# PCB-Relay-Board-V1.net
KiCad netlist of a schematic drawn in Altium Designer
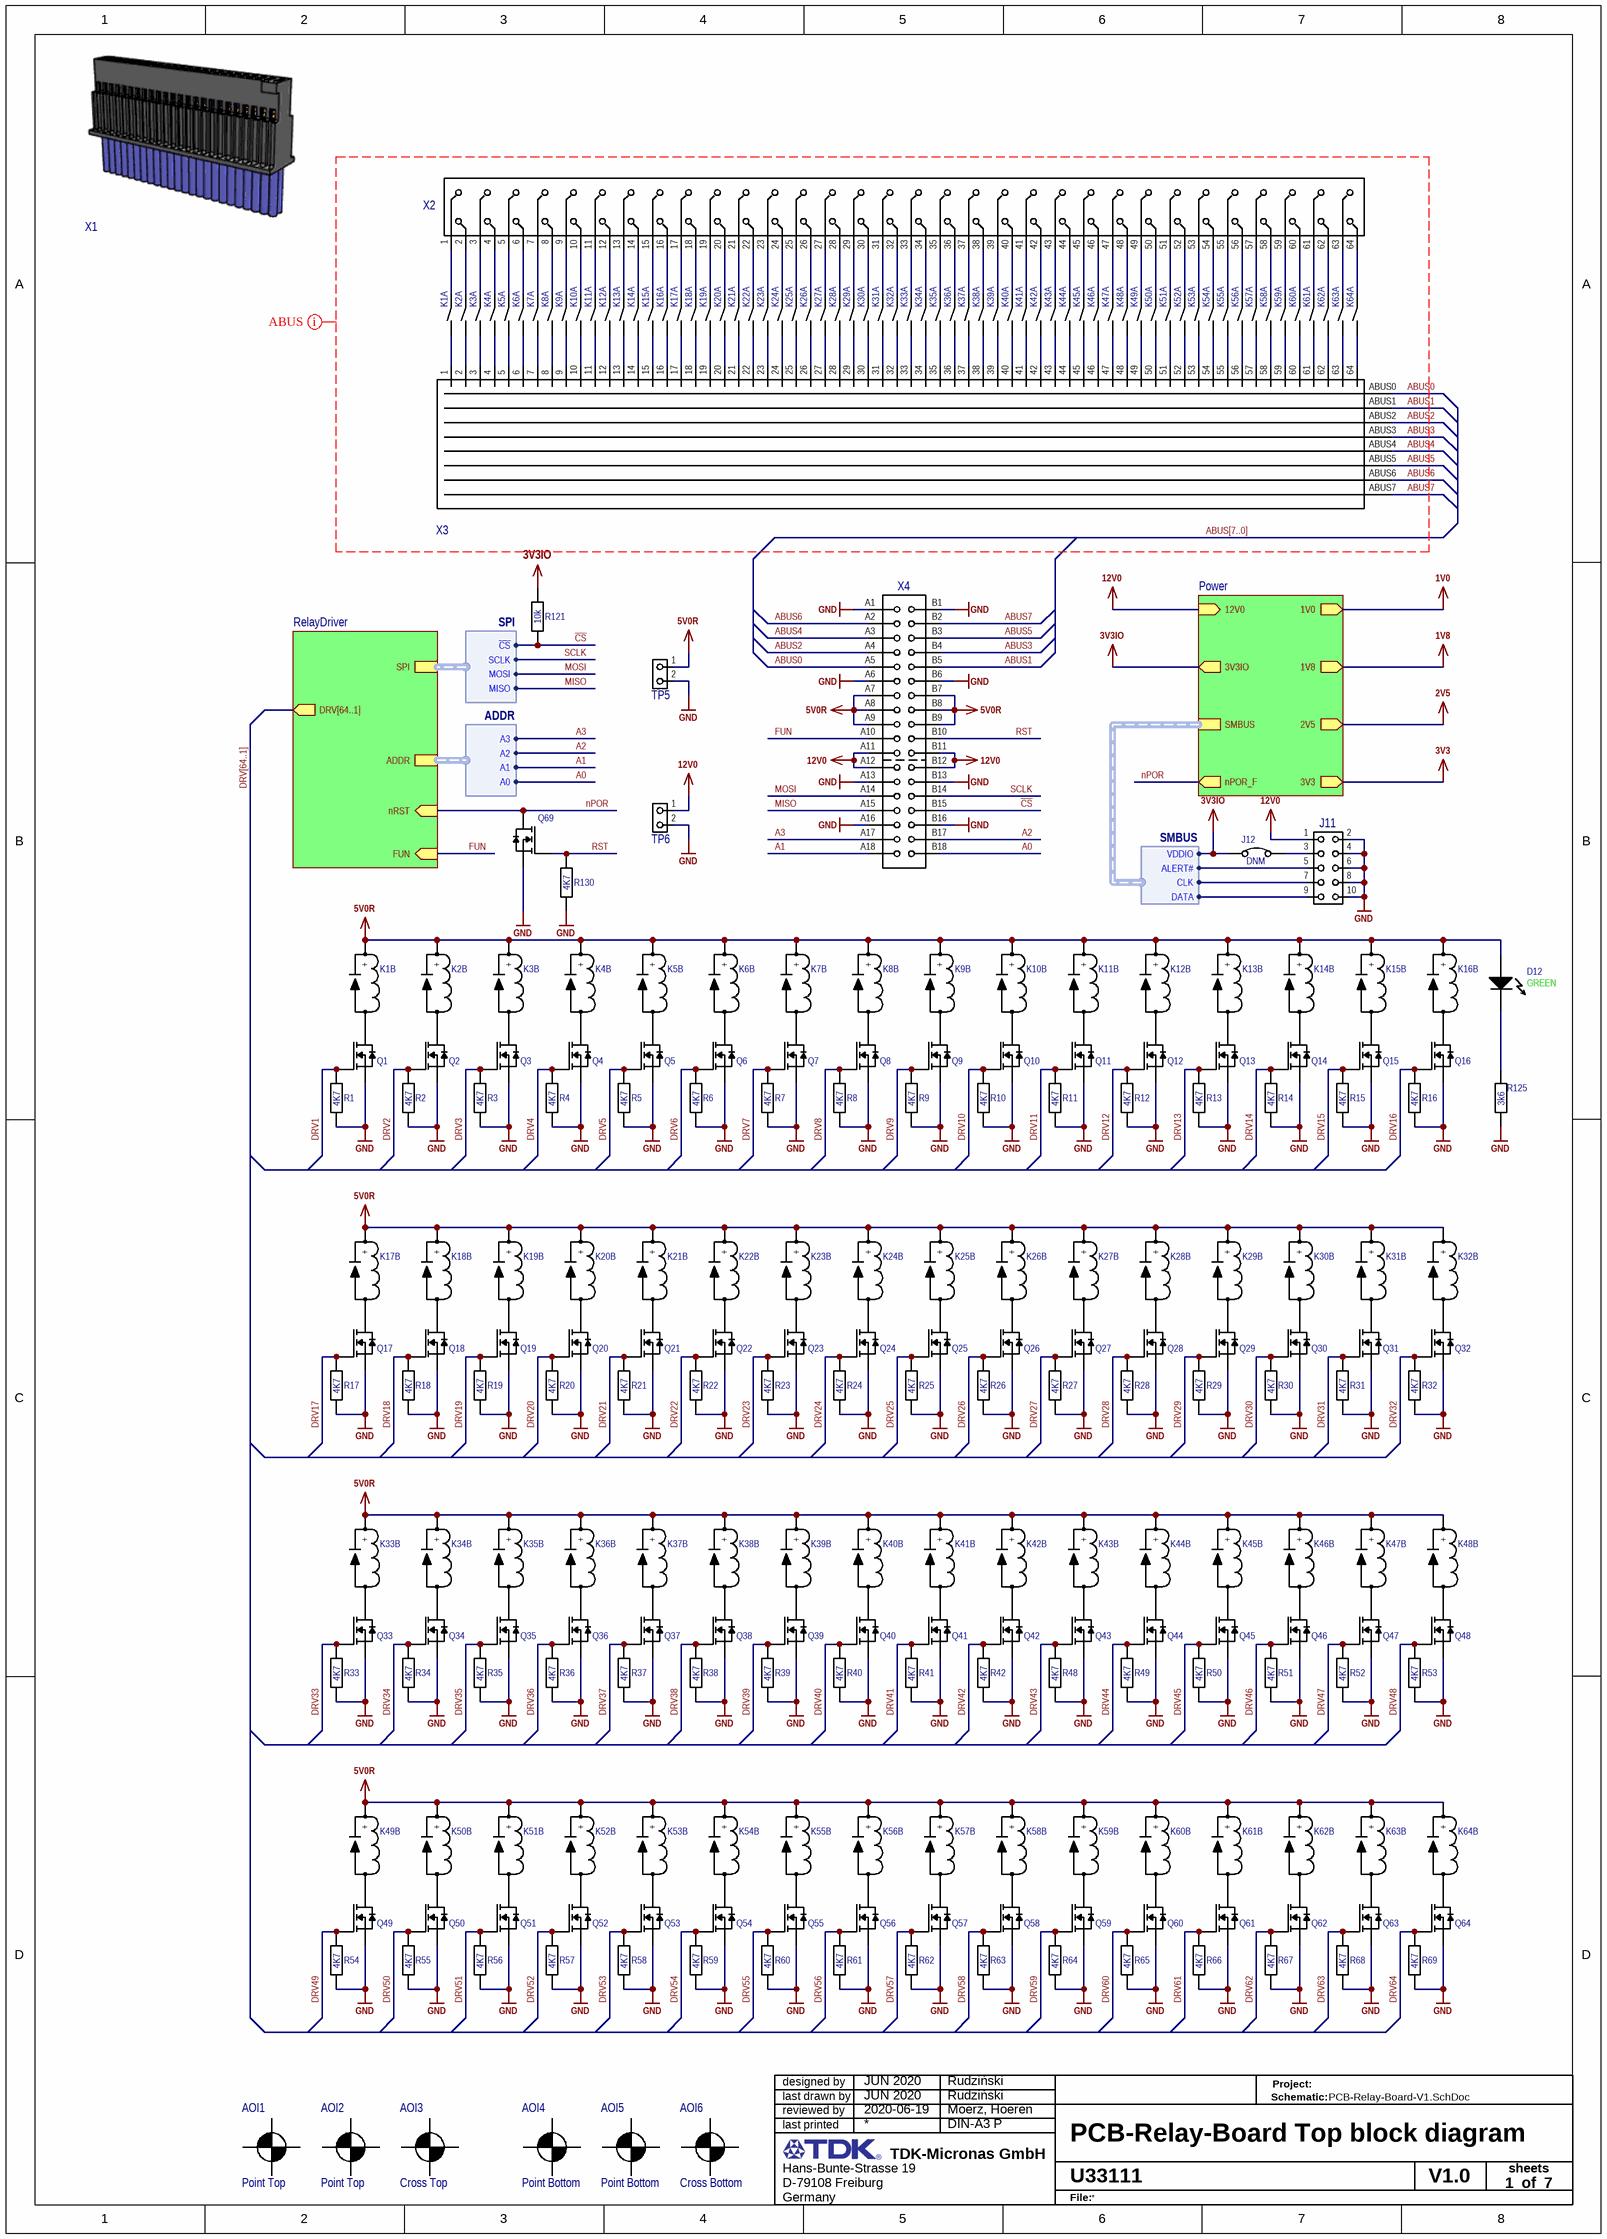
[diagram p0: PCB-Relay-Board-V1.SchDoc]

(export (version "E")
  (design (tool "Eeschema 10.0.6"))
  (components
    (comp (ref "AOI1")
      (value "AOI")
      (footprint "Fiducial Point")
      (description "Assembly AOI")
      (fields (field (name "SHAPE") "Point Top") (field (name "13. CREATED DATE/NAME") "AUG2018/Hören"))
      (libsource (lib "chickenfood") (part "Fiducial"))
    )
    (comp (ref "AOI2")
      (value "AOI")
      (footprint "Fiducial Point")
      (description "Assembly AOI")
      (fields (field (name "SHAPE") "Point Top") (field (name "13. CREATED DATE/NAME") "AUG2018/Hören"))
      (libsource (lib "chickenfood") (part "Fiducial"))
    )
    (comp (ref "AOI3")
      (value "AOI")
      (footprint "Fiducial Cross")
      (description "Assembly AOI")
      (fields (field (name "SHAPE") "Cross Top") (field (name "13. CREATED DATE/NAME") "AUG2018/Hören"))
      (libsource (lib "chickenfood") (part "Fiducial"))
    )
    (comp (ref "AOI4")
      (value "AOI")
      (footprint "Fiducial Point")
      (description "Assembly AOI")
      (fields (field (name "SHAPE") "Point Bottom") (field (name "13. CREATED DATE/NAME") "AUG2018/Hören"))
      (libsource (lib "chickenfood") (part "Fiducial"))
    )
    (comp (ref "AOI5")
      (value "AOI")
      (footprint "Fiducial Point")
      (description "Assembly AOI")
      (fields (field (name "SHAPE") "Point Bottom") (field (name "13. CREATED DATE/NAME") "AUG2018/Hören"))
      (libsource (lib "chickenfood") (part "Fiducial"))
    )
    (comp (ref "AOI6")
      (value "AOI")
      (footprint "Fiducial Cross")
      (description "Assembly AOI")
      (fields (field (name "SHAPE") "Cross Bottom") (field (name "13. CREATED DATE/NAME") "AUG2018/Hören"))
      (libsource (lib "chickenfood") (part "Fiducial"))
    )
    (comp (ref "D12")
      (value "D")
      (footprint "L0603G")
      (description "LED GREEN DIFFUSED 0603 SMD")
      (fields
        (field (name "02. DISTRIBUTOR PART NUMBER") "475-2709-6-ND")
        (field (name "07. MANUFACTURER  PART NUMBER") "LG L29K-G2J1-24-Z")
        (field (name "COLOR") "GREEN")
        (field (name "13. CREATED DATE/NAME") "AUG2018/Hören")
      )
      (libsource (lib "chickenfood") (part "LED"))
    )
    (comp (ref "J11")
      (value "J")
      (footprint "Header 100mil 5x2")
      (description ".100\" High-Temp Variable Post Height Terminal Strip")
      (fields
        (field (name "02. DISTRIBUTOR PART NUMBER") "HMTSW-105-07-G-D-240")
        (field (name "13. CREATED DATE/NAME") "AUG2018/Hören")
      )
      (libsource (lib "PCB-Tester-Board-V1") (part "Header 5x2Pins 100mil"))
    )
    (comp (ref "J12")
      (value "DNM")
      (footprint "JumperSMD")
      (description "RES SMD 0 OHM JUMPER 1/10W 0603")
      (fields
        (field (name "02. DISTRIBUTOR PART NUMBER") "311-0.0GRDKR-ND")
        (field (name "07. MANUFACTURER  PART NUMBER") "RC0603JR-070RL")
      )
      (libsource (lib "chickenfood") (part "Jumper SMD"))
    )
    (comp (ref "K1")
      (value "K")
      (footprint "118-1A")
      (description "5V Signal Relais, Normal Open")
      (fields
        (field (name "02. DISTRIBUTOR PART NUMBER") "118-1-A-5/2D")
        (field (name "13. CREATED DATE/NAME") "20.12.17 S. Kaiser")
      )
      (libsource (lib "chickenfood") (part "118-1-A-5/2D"))
    )
    (comp (ref "K2")
      (value "K")
      (footprint "118-1A")
      (description "5V Signal Relais, Normal Open")
      (fields
        (field (name "02. DISTRIBUTOR PART NUMBER") "118-1-A-5/2D")
        (field (name "13. CREATED DATE/NAME") "20.12.17 S. Kaiser")
      )
      (libsource (lib "chickenfood") (part "118-1-A-5/2D"))
    )
    (comp (ref "K3")
      (value "K")
      (footprint "118-1A")
      (description "5V Signal Relais, Normal Open")
      (fields
        (field (name "02. DISTRIBUTOR PART NUMBER") "118-1-A-5/2D")
        (field (name "13. CREATED DATE/NAME") "20.12.17 S. Kaiser")
      )
      (libsource (lib "") (part "118-1-A-5/2D_1"))
    )
    (comp (ref "K4")
      (value "K")
      (footprint "118-1A")
      (description "5V Signal Relais, Normal Open")
      (fields
        (field (name "02. DISTRIBUTOR PART NUMBER") "118-1-A-5/2D")
        (field (name "13. CREATED DATE/NAME") "20.12.17 S. Kaiser")
      )
      (libsource (lib "") (part "118-1-A-5/2D_1"))
    )
    (comp (ref "K5")
      (value "K")
      (footprint "118-1A")
      (description "5V Signal Relais, Normal Open")
      (fields
        (field (name "02. DISTRIBUTOR PART NUMBER") "118-1-A-5/2D")
        (field (name "13. CREATED DATE/NAME") "20.12.17 S. Kaiser")
      )
      (libsource (lib "") (part "118-1-A-5/2D_1"))
    )
    (comp (ref "K6")
      (value "K")
      (footprint "118-1A")
      (description "5V Signal Relais, Normal Open")
      (fields
        (field (name "02. DISTRIBUTOR PART NUMBER") "118-1-A-5/2D")
        (field (name "13. CREATED DATE/NAME") "20.12.17 S. Kaiser")
      )
      (libsource (lib "chickenfood") (part "118-1-A-5/2D"))
    )
    (comp (ref "K7")
      (value "K")
      (footprint "118-1A")
      (description "5V Signal Relais, Normal Open")
      (fields
        (field (name "02. DISTRIBUTOR PART NUMBER") "118-1-A-5/2D")
        (field (name "13. CREATED DATE/NAME") "20.12.17 S. Kaiser")
      )
      (libsource (lib "") (part "118-1-A-5/2D_1"))
    )
    (comp (ref "K8")
      (value "K")
      (footprint "118-1A")
      (description "5V Signal Relais, Normal Open")
      (fields
        (field (name "02. DISTRIBUTOR PART NUMBER") "118-1-A-5/2D")
        (field (name "13. CREATED DATE/NAME") "20.12.17 S. Kaiser")
      )
      (libsource (lib "chickenfood") (part "118-1-A-5/2D"))
    )
    (comp (ref "K9")
      (value "K")
      (footprint "118-1A")
      (description "5V Signal Relais, Normal Open")
      (fields
        (field (name "02. DISTRIBUTOR PART NUMBER") "118-1-A-5/2D")
        (field (name "13. CREATED DATE/NAME") "20.12.17 S. Kaiser")
      )
      (libsource (lib "chickenfood") (part "118-1-A-5/2D"))
    )
    (comp (ref "K10")
      (value "K")
      (footprint "118-1A")
      (description "5V Signal Relais, Normal Open")
      (fields
        (field (name "02. DISTRIBUTOR PART NUMBER") "118-1-A-5/2D")
        (field (name "13. CREATED DATE/NAME") "20.12.17 S. Kaiser")
      )
      (libsource (lib "") (part "118-1-A-5/2D_1"))
    )
    (comp (ref "K11")
      (value "K")
      (footprint "118-1A")
      (description "5V Signal Relais, Normal Open")
      (fields
        (field (name "02. DISTRIBUTOR PART NUMBER") "118-1-A-5/2D")
        (field (name "13. CREATED DATE/NAME") "20.12.17 S. Kaiser")
      )
      (libsource (lib "chickenfood") (part "118-1-A-5/2D"))
    )
    (comp (ref "K12")
      (value "K")
      (footprint "118-1A")
      (description "5V Signal Relais, Normal Open")
      (fields
        (field (name "02. DISTRIBUTOR PART NUMBER") "118-1-A-5/2D")
        (field (name "13. CREATED DATE/NAME") "20.12.17 S. Kaiser")
      )
      (libsource (lib "chickenfood") (part "118-1-A-5/2D"))
    )
    (comp (ref "K13")
      (value "K")
      (footprint "118-1A")
      (description "5V Signal Relais, Normal Open")
      (fields
        (field (name "02. DISTRIBUTOR PART NUMBER") "118-1-A-5/2D")
        (field (name "13. CREATED DATE/NAME") "20.12.17 S. Kaiser")
      )
      (libsource (lib "chickenfood") (part "118-1-A-5/2D"))
    )
    (comp (ref "K14")
      (value "K")
      (footprint "118-1A")
      (description "5V Signal Relais, Normal Open")
      (fields
        (field (name "02. DISTRIBUTOR PART NUMBER") "118-1-A-5/2D")
        (field (name "13. CREATED DATE/NAME") "20.12.17 S. Kaiser")
      )
      (libsource (lib "") (part "118-1-A-5/2D_1"))
    )
    (comp (ref "K15")
      (value "K")
      (footprint "118-1A")
      (description "5V Signal Relais, Normal Open")
      (fields
        (field (name "02. DISTRIBUTOR PART NUMBER") "118-1-A-5/2D")
        (field (name "13. CREATED DATE/NAME") "20.12.17 S. Kaiser")
      )
      (libsource (lib "chickenfood") (part "118-1-A-5/2D"))
    )
    (comp (ref "K16")
      (value "K")
      (footprint "118-1A")
      (description "5V Signal Relais, Normal Open")
      (fields
        (field (name "02. DISTRIBUTOR PART NUMBER") "118-1-A-5/2D")
        (field (name "13. CREATED DATE/NAME") "20.12.17 S. Kaiser")
      )
      (libsource (lib "") (part "118-1-A-5/2D_1"))
    )
    (comp (ref "K17")
      (value "K")
      (footprint "118-1A")
      (description "5V Signal Relais, Normal Open")
      (fields
        (field (name "02. DISTRIBUTOR PART NUMBER") "118-1-A-5/2D")
        (field (name "13. CREATED DATE/NAME") "20.12.17 S. Kaiser")
      )
      (libsource (lib "chickenfood") (part "118-1-A-5/2D"))
    )
    (comp (ref "K18")
      (value "K")
      (footprint "118-1A")
      (description "5V Signal Relais, Normal Open")
      (fields
        (field (name "02. DISTRIBUTOR PART NUMBER") "118-1-A-5/2D")
        (field (name "13. CREATED DATE/NAME") "20.12.17 S. Kaiser")
      )
      (libsource (lib "") (part "118-1-A-5/2D_1"))
    )
    (comp (ref "K19")
      (value "K")
      (footprint "118-1A")
      (description "5V Signal Relais, Normal Open")
      (fields
        (field (name "02. DISTRIBUTOR PART NUMBER") "118-1-A-5/2D")
        (field (name "13. CREATED DATE/NAME") "20.12.17 S. Kaiser")
      )
      (libsource (lib "") (part "118-1-A-5/2D_1"))
    )
    (comp (ref "K20")
      (value "K")
      (footprint "118-1A")
      (description "5V Signal Relais, Normal Open")
      (fields
        (field (name "02. DISTRIBUTOR PART NUMBER") "118-1-A-5/2D")
        (field (name "13. CREATED DATE/NAME") "20.12.17 S. Kaiser")
      )
      (libsource (lib "") (part "118-1-A-5/2D_1"))
    )
    (comp (ref "K21")
      (value "K")
      (footprint "118-1A")
      (description "5V Signal Relais, Normal Open")
      (fields
        (field (name "02. DISTRIBUTOR PART NUMBER") "118-1-A-5/2D")
        (field (name "13. CREATED DATE/NAME") "20.12.17 S. Kaiser")
      )
      (libsource (lib "") (part "118-1-A-5/2D_1"))
    )
    (comp (ref "K22")
      (value "K")
      (footprint "118-1A")
      (description "5V Signal Relais, Normal Open")
      (fields
        (field (name "02. DISTRIBUTOR PART NUMBER") "118-1-A-5/2D")
        (field (name "13. CREATED DATE/NAME") "20.12.17 S. Kaiser")
      )
      (libsource (lib "") (part "118-1-A-5/2D_1"))
    )
    (comp (ref "K23")
      (value "K")
      (footprint "118-1A")
      (description "5V Signal Relais, Normal Open")
      (fields
        (field (name "02. DISTRIBUTOR PART NUMBER") "118-1-A-5/2D")
        (field (name "13. CREATED DATE/NAME") "20.12.17 S. Kaiser")
      )
      (libsource (lib "chickenfood") (part "118-1-A-5/2D"))
    )
    (comp (ref "K24")
      (value "K")
      (footprint "118-1A")
      (description "5V Signal Relais, Normal Open")
      (fields
        (field (name "02. DISTRIBUTOR PART NUMBER") "118-1-A-5/2D")
        (field (name "13. CREATED DATE/NAME") "20.12.17 S. Kaiser")
      )
      (libsource (lib "") (part "118-1-A-5/2D_1"))
    )
    (comp (ref "K25")
      (value "K")
      (footprint "118-1A")
      (description "5V Signal Relais, Normal Open")
      (fields
        (field (name "02. DISTRIBUTOR PART NUMBER") "118-1-A-5/2D")
        (field (name "13. CREATED DATE/NAME") "20.12.17 S. Kaiser")
      )
      (libsource (lib "chickenfood") (part "118-1-A-5/2D"))
    )
    (comp (ref "K26")
      (value "K")
      (footprint "118-1A")
      (description "5V Signal Relais, Normal Open")
      (fields
        (field (name "02. DISTRIBUTOR PART NUMBER") "118-1-A-5/2D")
        (field (name "13. CREATED DATE/NAME") "20.12.17 S. Kaiser")
      )
      (libsource (lib "") (part "118-1-A-5/2D_1"))
    )
    (comp (ref "K27")
      (value "K")
      (footprint "118-1A")
      (description "5V Signal Relais, Normal Open")
      (fields
        (field (name "02. DISTRIBUTOR PART NUMBER") "118-1-A-5/2D")
        (field (name "13. CREATED DATE/NAME") "20.12.17 S. Kaiser")
      )
      (libsource (lib "chickenfood") (part "118-1-A-5/2D"))
    )
    (comp (ref "K28")
      (value "K")
      (footprint "118-1A")
      (description "5V Signal Relais, Normal Open")
      (fields
        (field (name "02. DISTRIBUTOR PART NUMBER") "118-1-A-5/2D")
        (field (name "13. CREATED DATE/NAME") "20.12.17 S. Kaiser")
      )
      (libsource (lib "") (part "118-1-A-5/2D_1"))
    )
    (comp (ref "K29")
      (value "K")
      (footprint "118-1A")
      (description "5V Signal Relais, Normal Open")
      (fields
        (field (name "02. DISTRIBUTOR PART NUMBER") "118-1-A-5/2D")
        (field (name "13. CREATED DATE/NAME") "20.12.17 S. Kaiser")
      )
      (libsource (lib "chickenfood") (part "118-1-A-5/2D"))
    )
    (comp (ref "K30")
      (value "K")
      (footprint "118-1A")
      (description "5V Signal Relais, Normal Open")
      (fields
        (field (name "02. DISTRIBUTOR PART NUMBER") "118-1-A-5/2D")
        (field (name "13. CREATED DATE/NAME") "20.12.17 S. Kaiser")
      )
      (libsource (lib "chickenfood") (part "118-1-A-5/2D"))
    )
    (comp (ref "K31")
      (value "K")
      (footprint "118-1A")
      (description "5V Signal Relais, Normal Open")
      (fields
        (field (name "02. DISTRIBUTOR PART NUMBER") "118-1-A-5/2D")
        (field (name "13. CREATED DATE/NAME") "20.12.17 S. Kaiser")
      )
      (libsource (lib "chickenfood") (part "118-1-A-5/2D"))
    )
    (comp (ref "K32")
      (value "K")
      (footprint "118-1A")
      (description "5V Signal Relais, Normal Open")
      (fields
        (field (name "02. DISTRIBUTOR PART NUMBER") "118-1-A-5/2D")
        (field (name "13. CREATED DATE/NAME") "20.12.17 S. Kaiser")
      )
      (libsource (lib "chickenfood") (part "118-1-A-5/2D"))
    )
    (comp (ref "K33")
      (value "K")
      (footprint "118-1A")
      (description "5V Signal Relais, Normal Open")
      (fields
        (field (name "02. DISTRIBUTOR PART NUMBER") "118-1-A-5/2D")
        (field (name "13. CREATED DATE/NAME") "20.12.17 S. Kaiser")
      )
      (libsource (lib "chickenfood") (part "118-1-A-5/2D"))
    )
    (comp (ref "K34")
      (value "K")
      (footprint "118-1A")
      (description "5V Signal Relais, Normal Open")
      (fields
        (field (name "02. DISTRIBUTOR PART NUMBER") "118-1-A-5/2D")
        (field (name "13. CREATED DATE/NAME") "20.12.17 S. Kaiser")
      )
      (libsource (lib "chickenfood") (part "118-1-A-5/2D"))
    )
    (comp (ref "K35")
      (value "K")
      (footprint "118-1A")
      (description "5V Signal Relais, Normal Open")
      (fields
        (field (name "02. DISTRIBUTOR PART NUMBER") "118-1-A-5/2D")
        (field (name "13. CREATED DATE/NAME") "20.12.17 S. Kaiser")
      )
      (libsource (lib "chickenfood") (part "118-1-A-5/2D"))
    )
    (comp (ref "K36")
      (value "K")
      (footprint "118-1A")
      (description "5V Signal Relais, Normal Open")
      (fields
        (field (name "02. DISTRIBUTOR PART NUMBER") "118-1-A-5/2D")
        (field (name "13. CREATED DATE/NAME") "20.12.17 S. Kaiser")
      )
      (libsource (lib "") (part "118-1-A-5/2D_1"))
    )
    (comp (ref "K37")
      (value "K")
      (footprint "118-1A")
      (description "5V Signal Relais, Normal Open")
      (fields
        (field (name "02. DISTRIBUTOR PART NUMBER") "118-1-A-5/2D")
        (field (name "13. CREATED DATE/NAME") "20.12.17 S. Kaiser")
      )
      (libsource (lib "") (part "118-1-A-5/2D_1"))
    )
    (comp (ref "K38")
      (value "K")
      (footprint "118-1A")
      (description "5V Signal Relais, Normal Open")
      (fields
        (field (name "02. DISTRIBUTOR PART NUMBER") "118-1-A-5/2D")
        (field (name "13. CREATED DATE/NAME") "20.12.17 S. Kaiser")
      )
      (libsource (lib "") (part "118-1-A-5/2D_1"))
    )
    (comp (ref "K39")
      (value "K")
      (footprint "118-1A")
      (description "5V Signal Relais, Normal Open")
      (fields
        (field (name "02. DISTRIBUTOR PART NUMBER") "118-1-A-5/2D")
        (field (name "13. CREATED DATE/NAME") "20.12.17 S. Kaiser")
      )
      (libsource (lib "chickenfood") (part "118-1-A-5/2D"))
    )
    (comp (ref "K40")
      (value "K")
      (footprint "118-1A")
      (description "5V Signal Relais, Normal Open")
      (fields
        (field (name "02. DISTRIBUTOR PART NUMBER") "118-1-A-5/2D")
        (field (name "13. CREATED DATE/NAME") "20.12.17 S. Kaiser")
      )
      (libsource (lib "") (part "118-1-A-5/2D_1"))
    )
    (comp (ref "K41")
      (value "K")
      (footprint "118-1A")
      (description "5V Signal Relais, Normal Open")
      (fields
        (field (name "02. DISTRIBUTOR PART NUMBER") "118-1-A-5/2D")
        (field (name "13. CREATED DATE/NAME") "20.12.17 S. Kaiser")
      )
      (libsource (lib "") (part "118-1-A-5/2D_1"))
    )
    (comp (ref "K42")
      (value "K")
      (footprint "118-1A")
      (description "5V Signal Relais, Normal Open")
      (fields
        (field (name "02. DISTRIBUTOR PART NUMBER") "118-1-A-5/2D")
        (field (name "13. CREATED DATE/NAME") "20.12.17 S. Kaiser")
      )
      (libsource (lib "chickenfood") (part "118-1-A-5/2D"))
    )
    (comp (ref "K43")
      (value "K")
      (footprint "118-1A")
      (description "5V Signal Relais, Normal Open")
      (fields
        (field (name "02. DISTRIBUTOR PART NUMBER") "118-1-A-5/2D")
        (field (name "13. CREATED DATE/NAME") "20.12.17 S. Kaiser")
      )
      (libsource (lib "chickenfood") (part "118-1-A-5/2D"))
    )
    (comp (ref "K44")
      (value "K")
      (footprint "118-1A")
      (description "5V Signal Relais, Normal Open")
      (fields
        (field (name "02. DISTRIBUTOR PART NUMBER") "118-1-A-5/2D")
        (field (name "13. CREATED DATE/NAME") "20.12.17 S. Kaiser")
      )
      (libsource (lib "") (part "118-1-A-5/2D_1"))
    )
    (comp (ref "K45")
      (value "K")
      (footprint "118-1A")
      (description "5V Signal Relais, Normal Open")
      (fields
        (field (name "02. DISTRIBUTOR PART NUMBER") "118-1-A-5/2D")
        (field (name "13. CREATED DATE/NAME") "20.12.17 S. Kaiser")
      )
      (libsource (lib "") (part "118-1-A-5/2D_1"))
    )
    (comp (ref "K46")
      (value "K")
      (footprint "118-1A")
      (description "5V Signal Relais, Normal Open")
      (fields
        (field (name "02. DISTRIBUTOR PART NUMBER") "118-1-A-5/2D")
        (field (name "13. CREATED DATE/NAME") "20.12.17 S. Kaiser")
      )
      (libsource (lib "") (part "118-1-A-5/2D_1"))
    )
    (comp (ref "K47")
      (value "K")
      (footprint "118-1A")
      (description "5V Signal Relais, Normal Open")
      (fields
        (field (name "02. DISTRIBUTOR PART NUMBER") "118-1-A-5/2D")
        (field (name "13. CREATED DATE/NAME") "20.12.17 S. Kaiser")
      )
      (libsource (lib "") (part "118-1-A-5/2D_1"))
    )
    (comp (ref "K48")
      (value "K")
      (footprint "118-1A")
      (description "5V Signal Relais, Normal Open")
      (fields
        (field (name "02. DISTRIBUTOR PART NUMBER") "118-1-A-5/2D")
        (field (name "13. CREATED DATE/NAME") "20.12.17 S. Kaiser")
      )
      (libsource (lib "") (part "118-1-A-5/2D_1"))
    )
    (comp (ref "K49")
      (value "K")
      (footprint "118-1A")
      (description "5V Signal Relais, Normal Open")
      (fields
        (field (name "02. DISTRIBUTOR PART NUMBER") "118-1-A-5/2D")
        (field (name "13. CREATED DATE/NAME") "20.12.17 S. Kaiser")
      )
      (libsource (lib "chickenfood") (part "118-1-A-5/2D"))
    )
    (comp (ref "K50")
      (value "K")
      (footprint "118-1A")
      (description "5V Signal Relais, Normal Open")
      (fields
        (field (name "02. DISTRIBUTOR PART NUMBER") "118-1-A-5/2D")
        (field (name "13. CREATED DATE/NAME") "20.12.17 S. Kaiser")
      )
      (libsource (lib "chickenfood") (part "118-1-A-5/2D"))
    )
    (comp (ref "K51")
      (value "K")
      (footprint "118-1A")
      (description "5V Signal Relais, Normal Open")
      (fields
        (field (name "02. DISTRIBUTOR PART NUMBER") "118-1-A-5/2D")
        (field (name "13. CREATED DATE/NAME") "20.12.17 S. Kaiser")
      )
      (libsource (lib "chickenfood") (part "118-1-A-5/2D"))
    )
    (comp (ref "K52")
      (value "K")
      (footprint "118-1A")
      (description "5V Signal Relais, Normal Open")
      (fields
        (field (name "02. DISTRIBUTOR PART NUMBER") "118-1-A-5/2D")
        (field (name "13. CREATED DATE/NAME") "20.12.17 S. Kaiser")
      )
      (libsource (lib "") (part "118-1-A-5/2D_1"))
    )
    (comp (ref "K53")
      (value "K")
      (footprint "118-1A")
      (description "5V Signal Relais, Normal Open")
      (fields
        (field (name "02. DISTRIBUTOR PART NUMBER") "118-1-A-5/2D")
        (field (name "13. CREATED DATE/NAME") "20.12.17 S. Kaiser")
      )
      (libsource (lib "chickenfood") (part "118-1-A-5/2D"))
    )
    (comp (ref "K54")
      (value "K")
      (footprint "118-1A")
      (description "5V Signal Relais, Normal Open")
      (fields
        (field (name "02. DISTRIBUTOR PART NUMBER") "118-1-A-5/2D")
        (field (name "13. CREATED DATE/NAME") "20.12.17 S. Kaiser")
      )
      (libsource (lib "chickenfood") (part "118-1-A-5/2D"))
    )
    (comp (ref "K55")
      (value "K")
      (footprint "118-1A")
      (description "5V Signal Relais, Normal Open")
      (fields
        (field (name "02. DISTRIBUTOR PART NUMBER") "118-1-A-5/2D")
        (field (name "13. CREATED DATE/NAME") "20.12.17 S. Kaiser")
      )
      (libsource (lib "chickenfood") (part "118-1-A-5/2D"))
    )
    (comp (ref "K56")
      (value "K")
      (footprint "118-1A")
      (description "5V Signal Relais, Normal Open")
      (fields
        (field (name "02. DISTRIBUTOR PART NUMBER") "118-1-A-5/2D")
        (field (name "13. CREATED DATE/NAME") "20.12.17 S. Kaiser")
      )
      (libsource (lib "") (part "118-1-A-5/2D_1"))
    )
    (comp (ref "K57")
      (value "K")
      (footprint "118-1A")
      (description "5V Signal Relais, Normal Open")
      (fields
        (field (name "02. DISTRIBUTOR PART NUMBER") "118-1-A-5/2D")
        (field (name "13. CREATED DATE/NAME") "20.12.17 S. Kaiser")
      )
      (libsource (lib "") (part "118-1-A-5/2D_1"))
    )
    (comp (ref "K58")
      (value "K")
      (footprint "118-1A")
      (description "5V Signal Relais, Normal Open")
      (fields
        (field (name "02. DISTRIBUTOR PART NUMBER") "118-1-A-5/2D")
        (field (name "13. CREATED DATE/NAME") "20.12.17 S. Kaiser")
      )
      (libsource (lib "chickenfood") (part "118-1-A-5/2D"))
    )
    (comp (ref "K59")
      (value "K")
      (footprint "118-1A")
      (description "5V Signal Relais, Normal Open")
      (fields
        (field (name "02. DISTRIBUTOR PART NUMBER") "118-1-A-5/2D")
        (field (name "13. CREATED DATE/NAME") "20.12.17 S. Kaiser")
      )
      (libsource (lib "chickenfood") (part "118-1-A-5/2D"))
    )
    (comp (ref "K60")
      (value "K")
      (footprint "118-1A")
      (description "5V Signal Relais, Normal Open")
      (fields
        (field (name "02. DISTRIBUTOR PART NUMBER") "118-1-A-5/2D")
        (field (name "13. CREATED DATE/NAME") "20.12.17 S. Kaiser")
      )
      (libsource (lib "") (part "118-1-A-5/2D_1"))
    )
    (comp (ref "K61")
      (value "K")
      (footprint "118-1A")
      (description "5V Signal Relais, Normal Open")
      (fields
        (field (name "02. DISTRIBUTOR PART NUMBER") "118-1-A-5/2D")
        (field (name "13. CREATED DATE/NAME") "20.12.17 S. Kaiser")
      )
      (libsource (lib "chickenfood") (part "118-1-A-5/2D"))
    )
    (comp (ref "K62")
      (value "K")
      (footprint "118-1A")
      (description "5V Signal Relais, Normal Open")
      (fields
        (field (name "02. DISTRIBUTOR PART NUMBER") "118-1-A-5/2D")
        (field (name "13. CREATED DATE/NAME") "20.12.17 S. Kaiser")
      )
      (libsource (lib "chickenfood") (part "118-1-A-5/2D"))
    )
    (comp (ref "K63")
      (value "K")
      (footprint "118-1A")
      (description "5V Signal Relais, Normal Open")
      (fields
        (field (name "02. DISTRIBUTOR PART NUMBER") "118-1-A-5/2D")
        (field (name "13. CREATED DATE/NAME") "20.12.17 S. Kaiser")
      )
      (libsource (lib "") (part "118-1-A-5/2D_1"))
    )
    (comp (ref "K64")
      (value "K")
      (footprint "118-1A")
      (description "5V Signal Relais, Normal Open")
      (fields
        (field (name "02. DISTRIBUTOR PART NUMBER") "118-1-A-5/2D")
        (field (name "13. CREATED DATE/NAME") "20.12.17 S. Kaiser")
      )
      (libsource (lib "") (part "118-1-A-5/2D_1"))
    )
    (comp (ref "Q1")
      (value "Q")
      (footprint "SOT23-3")
      (description "MOSFET N-CH 25V 680MA SOT-23")
      (fields
        (field (name "02. DISTRIBUTOR PART NUMBER") "FDV303NDKR-ND")
        (field (name "07. MANUFACTURER  PART NUMBER") "FDV303N")
        (field (name "13. CREATED DATE/NAME") "AUG 2018 / Hören")
      )
      (libsource (lib "SCT8-Board1") (part "FDV303N"))
    )
    (comp (ref "Q2")
      (value "Q")
      (footprint "SOT23-3")
      (description "MOSFET N-CH 25V 680MA SOT-23")
      (fields
        (field (name "02. DISTRIBUTOR PART NUMBER") "FDV303NDKR-ND")
        (field (name "07. MANUFACTURER  PART NUMBER") "FDV303N")
        (field (name "13. CREATED DATE/NAME") "AUG 2018 / Hören")
      )
      (libsource (lib "SCT8-Board1") (part "FDV303N"))
    )
    (comp (ref "Q3")
      (value "Q")
      (footprint "SOT23-3")
      (description "MOSFET N-CH 25V 680MA SOT-23")
      (fields
        (field (name "02. DISTRIBUTOR PART NUMBER") "FDV303NDKR-ND")
        (field (name "07. MANUFACTURER  PART NUMBER") "FDV303N")
        (field (name "13. CREATED DATE/NAME") "AUG 2018 / Hören")
      )
      (libsource (lib "SCT8-Board1") (part "FDV303N"))
    )
    (comp (ref "Q4")
      (value "Q")
      (footprint "SOT23-3")
      (description "MOSFET N-CH 25V 680MA SOT-23")
      (fields
        (field (name "02. DISTRIBUTOR PART NUMBER") "FDV303NDKR-ND")
        (field (name "07. MANUFACTURER  PART NUMBER") "FDV303N")
        (field (name "13. CREATED DATE/NAME") "AUG 2018 / Hören")
      )
      (libsource (lib "SCT8-Board1") (part "FDV303N"))
    )
    (comp (ref "Q5")
      (value "Q")
      (footprint "SOT23-3")
      (description "MOSFET N-CH 25V 680MA SOT-23")
      (fields
        (field (name "02. DISTRIBUTOR PART NUMBER") "FDV303NDKR-ND")
        (field (name "07. MANUFACTURER  PART NUMBER") "FDV303N")
        (field (name "13. CREATED DATE/NAME") "AUG 2018 / Hören")
      )
      (libsource (lib "SCT8-Board1") (part "FDV303N"))
    )
    (comp (ref "Q6")
      (value "Q")
      (footprint "SOT23-3")
      (description "MOSFET N-CH 25V 680MA SOT-23")
      (fields
        (field (name "02. DISTRIBUTOR PART NUMBER") "FDV303NDKR-ND")
        (field (name "07. MANUFACTURER  PART NUMBER") "FDV303N")
        (field (name "13. CREATED DATE/NAME") "AUG 2018 / Hören")
      )
      (libsource (lib "SCT8-Board1") (part "FDV303N"))
    )
    (comp (ref "Q7")
      (value "Q")
      (footprint "SOT23-3")
      (description "MOSFET N-CH 25V 680MA SOT-23")
      (fields
        (field (name "02. DISTRIBUTOR PART NUMBER") "FDV303NDKR-ND")
        (field (name "07. MANUFACTURER  PART NUMBER") "FDV303N")
        (field (name "13. CREATED DATE/NAME") "AUG 2018 / Hören")
      )
      (libsource (lib "SCT8-Board1") (part "FDV303N"))
    )
    (comp (ref "Q8")
      (value "Q")
      (footprint "SOT23-3")
      (description "MOSFET N-CH 25V 680MA SOT-23")
      (fields
        (field (name "02. DISTRIBUTOR PART NUMBER") "FDV303NDKR-ND")
        (field (name "07. MANUFACTURER  PART NUMBER") "FDV303N")
        (field (name "13. CREATED DATE/NAME") "AUG 2018 / Hören")
      )
      (libsource (lib "SCT8-Board1") (part "FDV303N"))
    )
    (comp (ref "Q9")
      (value "Q")
      (footprint "SOT23-3")
      (description "MOSFET N-CH 25V 680MA SOT-23")
      (fields
        (field (name "02. DISTRIBUTOR PART NUMBER") "FDV303NDKR-ND")
        (field (name "07. MANUFACTURER  PART NUMBER") "FDV303N")
        (field (name "13. CREATED DATE/NAME") "AUG 2018 / Hören")
      )
      (libsource (lib "SCT8-Board1") (part "FDV303N"))
    )
    (comp (ref "Q10")
      (value "Q")
      (footprint "SOT23-3")
      (description "MOSFET N-CH 25V 680MA SOT-23")
      (fields
        (field (name "02. DISTRIBUTOR PART NUMBER") "FDV303NDKR-ND")
        (field (name "07. MANUFACTURER  PART NUMBER") "FDV303N")
        (field (name "13. CREATED DATE/NAME") "AUG 2018 / Hören")
      )
      (libsource (lib "SCT8-Board1") (part "FDV303N"))
    )
    (comp (ref "Q11")
      (value "Q")
      (footprint "SOT23-3")
      (description "MOSFET N-CH 25V 680MA SOT-23")
      (fields
        (field (name "02. DISTRIBUTOR PART NUMBER") "FDV303NDKR-ND")
        (field (name "07. MANUFACTURER  PART NUMBER") "FDV303N")
        (field (name "13. CREATED DATE/NAME") "AUG 2018 / Hören")
      )
      (libsource (lib "SCT8-Board1") (part "FDV303N"))
    )
    (comp (ref "Q12")
      (value "Q")
      (footprint "SOT23-3")
      (description "MOSFET N-CH 25V 680MA SOT-23")
      (fields
        (field (name "02. DISTRIBUTOR PART NUMBER") "FDV303NDKR-ND")
        (field (name "07. MANUFACTURER  PART NUMBER") "FDV303N")
        (field (name "13. CREATED DATE/NAME") "AUG 2018 / Hören")
      )
      (libsource (lib "SCT8-Board1") (part "FDV303N"))
    )
    (comp (ref "Q13")
      (value "Q")
      (footprint "SOT23-3")
      (description "MOSFET N-CH 25V 680MA SOT-23")
      (fields
        (field (name "02. DISTRIBUTOR PART NUMBER") "FDV303NDKR-ND")
        (field (name "07. MANUFACTURER  PART NUMBER") "FDV303N")
        (field (name "13. CREATED DATE/NAME") "AUG 2018 / Hören")
      )
      (libsource (lib "SCT8-Board1") (part "FDV303N"))
    )
    (comp (ref "Q14")
      (value "Q")
      (footprint "SOT23-3")
      (description "MOSFET N-CH 25V 680MA SOT-23")
      (fields
        (field (name "02. DISTRIBUTOR PART NUMBER") "FDV303NDKR-ND")
        (field (name "07. MANUFACTURER  PART NUMBER") "FDV303N")
        (field (name "13. CREATED DATE/NAME") "AUG 2018 / Hören")
      )
      (libsource (lib "SCT8-Board1") (part "FDV303N"))
    )
    (comp (ref "Q15")
      (value "Q")
      (footprint "SOT23-3")
      (description "MOSFET N-CH 25V 680MA SOT-23")
      (fields
        (field (name "02. DISTRIBUTOR PART NUMBER") "FDV303NDKR-ND")
        (field (name "07. MANUFACTURER  PART NUMBER") "FDV303N")
        (field (name "13. CREATED DATE/NAME") "AUG 2018 / Hören")
      )
      (libsource (lib "SCT8-Board1") (part "FDV303N"))
    )
    (comp (ref "Q16")
      (value "Q")
      (footprint "SOT23-3")
      (description "MOSFET N-CH 25V 680MA SOT-23")
      (fields
        (field (name "02. DISTRIBUTOR PART NUMBER") "FDV303NDKR-ND")
        (field (name "07. MANUFACTURER  PART NUMBER") "FDV303N")
        (field (name "13. CREATED DATE/NAME") "AUG 2018 / Hören")
      )
      (libsource (lib "SCT8-Board1") (part "FDV303N"))
    )
    (comp (ref "Q17")
      (value "Q")
      (footprint "SOT23-3")
      (description "MOSFET N-CH 25V 680MA SOT-23")
      (fields
        (field (name "02. DISTRIBUTOR PART NUMBER") "FDV303NDKR-ND")
        (field (name "07. MANUFACTURER  PART NUMBER") "FDV303N")
        (field (name "13. CREATED DATE/NAME") "AUG 2018 / Hören")
      )
      (libsource (lib "SCT8-Board1") (part "FDV303N"))
    )
    (comp (ref "Q18")
      (value "Q")
      (footprint "SOT23-3")
      (description "MOSFET N-CH 25V 680MA SOT-23")
      (fields
        (field (name "02. DISTRIBUTOR PART NUMBER") "FDV303NDKR-ND")
        (field (name "07. MANUFACTURER  PART NUMBER") "FDV303N")
        (field (name "13. CREATED DATE/NAME") "AUG 2018 / Hören")
      )
      (libsource (lib "SCT8-Board1") (part "FDV303N"))
    )
    (comp (ref "Q19")
      (value "Q")
      (footprint "SOT23-3")
      (description "MOSFET N-CH 25V 680MA SOT-23")
      (fields
        (field (name "02. DISTRIBUTOR PART NUMBER") "FDV303NDKR-ND")
        (field (name "07. MANUFACTURER  PART NUMBER") "FDV303N")
        (field (name "13. CREATED DATE/NAME") "AUG 2018 / Hören")
      )
      (libsource (lib "SCT8-Board1") (part "FDV303N"))
    )
    (comp (ref "Q20")
      (value "Q")
      (footprint "SOT23-3")
      (description "MOSFET N-CH 25V 680MA SOT-23")
      (fields
        (field (name "02. DISTRIBUTOR PART NUMBER") "FDV303NDKR-ND")
        (field (name "07. MANUFACTURER  PART NUMBER") "FDV303N")
        (field (name "13. CREATED DATE/NAME") "AUG 2018 / Hören")
      )
      (libsource (lib "SCT8-Board1") (part "FDV303N"))
    )
    (comp (ref "Q21")
      (value "Q")
      (footprint "SOT23-3")
      (description "MOSFET N-CH 25V 680MA SOT-23")
      (fields
        (field (name "02. DISTRIBUTOR PART NUMBER") "FDV303NDKR-ND")
        (field (name "07. MANUFACTURER  PART NUMBER") "FDV303N")
        (field (name "13. CREATED DATE/NAME") "AUG 2018 / Hören")
      )
      (libsource (lib "SCT8-Board1") (part "FDV303N"))
    )
    (comp (ref "Q22")
      (value "Q")
      (footprint "SOT23-3")
      (description "MOSFET N-CH 25V 680MA SOT-23")
      (fields
        (field (name "02. DISTRIBUTOR PART NUMBER") "FDV303NDKR-ND")
        (field (name "07. MANUFACTURER  PART NUMBER") "FDV303N")
        (field (name "13. CREATED DATE/NAME") "AUG 2018 / Hören")
      )
      (libsource (lib "SCT8-Board1") (part "FDV303N"))
    )
    (comp (ref "Q23")
      (value "Q")
      (footprint "SOT23-3")
      (description "MOSFET N-CH 25V 680MA SOT-23")
      (fields
        (field (name "02. DISTRIBUTOR PART NUMBER") "FDV303NDKR-ND")
        (field (name "07. MANUFACTURER  PART NUMBER") "FDV303N")
        (field (name "13. CREATED DATE/NAME") "AUG 2018 / Hören")
      )
      (libsource (lib "SCT8-Board1") (part "FDV303N"))
    )
    (comp (ref "Q24")
      (value "Q")
      (footprint "SOT23-3")
      (description "MOSFET N-CH 25V 680MA SOT-23")
      (fields
        (field (name "02. DISTRIBUTOR PART NUMBER") "FDV303NDKR-ND")
        (field (name "07. MANUFACTURER  PART NUMBER") "FDV303N")
        (field (name "13. CREATED DATE/NAME") "AUG 2018 / Hören")
      )
      (libsource (lib "SCT8-Board1") (part "FDV303N"))
    )
    (comp (ref "Q25")
      (value "Q")
      (footprint "SOT23-3")
      (description "MOSFET N-CH 25V 680MA SOT-23")
      (fields
        (field (name "02. DISTRIBUTOR PART NUMBER") "FDV303NDKR-ND")
        (field (name "07. MANUFACTURER  PART NUMBER") "FDV303N")
        (field (name "13. CREATED DATE/NAME") "AUG 2018 / Hören")
      )
      (libsource (lib "SCT8-Board1") (part "FDV303N"))
    )
    (comp (ref "Q26")
      (value "Q")
      (footprint "SOT23-3")
      (description "MOSFET N-CH 25V 680MA SOT-23")
      (fields
        (field (name "02. DISTRIBUTOR PART NUMBER") "FDV303NDKR-ND")
        (field (name "07. MANUFACTURER  PART NUMBER") "FDV303N")
        (field (name "13. CREATED DATE/NAME") "AUG 2018 / Hören")
      )
      (libsource (lib "SCT8-Board1") (part "FDV303N"))
    )
    (comp (ref "Q27")
      (value "Q")
      (footprint "SOT23-3")
      (description "MOSFET N-CH 25V 680MA SOT-23")
      (fields
        (field (name "02. DISTRIBUTOR PART NUMBER") "FDV303NDKR-ND")
        (field (name "07. MANUFACTURER  PART NUMBER") "FDV303N")
        (field (name "13. CREATED DATE/NAME") "AUG 2018 / Hören")
      )
      (libsource (lib "SCT8-Board1") (part "FDV303N"))
    )
    (comp (ref "Q28")
      (value "Q")
      (footprint "SOT23-3")
      (description "MOSFET N-CH 25V 680MA SOT-23")
      (fields
        (field (name "02. DISTRIBUTOR PART NUMBER") "FDV303NDKR-ND")
        (field (name "07. MANUFACTURER  PART NUMBER") "FDV303N")
        (field (name "13. CREATED DATE/NAME") "AUG 2018 / Hören")
      )
      (libsource (lib "SCT8-Board1") (part "FDV303N"))
    )
    (comp (ref "Q29")
      (value "Q")
      (footprint "SOT23-3")
      (description "MOSFET N-CH 25V 680MA SOT-23")
      (fields
        (field (name "02. DISTRIBUTOR PART NUMBER") "FDV303NDKR-ND")
        (field (name "07. MANUFACTURER  PART NUMBER") "FDV303N")
        (field (name "13. CREATED DATE/NAME") "AUG 2018 / Hören")
      )
      (libsource (lib "SCT8-Board1") (part "FDV303N"))
    )
    (comp (ref "Q30")
      (value "Q")
      (footprint "SOT23-3")
      (description "MOSFET N-CH 25V 680MA SOT-23")
      (fields
        (field (name "02. DISTRIBUTOR PART NUMBER") "FDV303NDKR-ND")
        (field (name "07. MANUFACTURER  PART NUMBER") "FDV303N")
        (field (name "13. CREATED DATE/NAME") "AUG 2018 / Hören")
      )
      (libsource (lib "SCT8-Board1") (part "FDV303N"))
    )
    (comp (ref "Q31")
      (value "Q")
      (footprint "SOT23-3")
      (description "MOSFET N-CH 25V 680MA SOT-23")
      (fields
        (field (name "02. DISTRIBUTOR PART NUMBER") "FDV303NDKR-ND")
        (field (name "07. MANUFACTURER  PART NUMBER") "FDV303N")
        (field (name "13. CREATED DATE/NAME") "AUG 2018 / Hören")
      )
      (libsource (lib "SCT8-Board1") (part "FDV303N"))
    )
    (comp (ref "Q32")
      (value "Q")
      (footprint "SOT23-3")
      (description "MOSFET N-CH 25V 680MA SOT-23")
      (fields
        (field (name "02. DISTRIBUTOR PART NUMBER") "FDV303NDKR-ND")
        (field (name "07. MANUFACTURER  PART NUMBER") "FDV303N")
        (field (name "13. CREATED DATE/NAME") "AUG 2018 / Hören")
      )
      (libsource (lib "SCT8-Board1") (part "FDV303N"))
    )
    (comp (ref "Q33")
      (value "Q")
      (footprint "SOT23-3")
      (description "MOSFET N-CH 25V 680MA SOT-23")
      (fields
        (field (name "02. DISTRIBUTOR PART NUMBER") "FDV303NDKR-ND")
        (field (name "07. MANUFACTURER  PART NUMBER") "FDV303N")
        (field (name "13. CREATED DATE/NAME") "AUG 2018 / Hören")
      )
      (libsource (lib "SCT8-Board1") (part "FDV303N"))
    )
    (comp (ref "Q34")
      (value "Q")
      (footprint "SOT23-3")
      (description "MOSFET N-CH 25V 680MA SOT-23")
      (fields
        (field (name "02. DISTRIBUTOR PART NUMBER") "FDV303NDKR-ND")
        (field (name "07. MANUFACTURER  PART NUMBER") "FDV303N")
        (field (name "13. CREATED DATE/NAME") "AUG 2018 / Hören")
      )
      (libsource (lib "SCT8-Board1") (part "FDV303N"))
    )
    (comp (ref "Q35")
      (value "Q")
      (footprint "SOT23-3")
      (description "MOSFET N-CH 25V 680MA SOT-23")
      (fields
        (field (name "02. DISTRIBUTOR PART NUMBER") "FDV303NDKR-ND")
        (field (name "07. MANUFACTURER  PART NUMBER") "FDV303N")
        (field (name "13. CREATED DATE/NAME") "AUG 2018 / Hören")
      )
      (libsource (lib "SCT8-Board1") (part "FDV303N"))
    )
    (comp (ref "Q36")
      (value "Q")
      (footprint "SOT23-3")
      (description "MOSFET N-CH 25V 680MA SOT-23")
      (fields
        (field (name "02. DISTRIBUTOR PART NUMBER") "FDV303NDKR-ND")
        (field (name "07. MANUFACTURER  PART NUMBER") "FDV303N")
        (field (name "13. CREATED DATE/NAME") "AUG 2018 / Hören")
      )
      (libsource (lib "SCT8-Board1") (part "FDV303N"))
    )
    (comp (ref "Q37")
      (value "Q")
      (footprint "SOT23-3")
      (description "MOSFET N-CH 25V 680MA SOT-23")
      (fields
        (field (name "02. DISTRIBUTOR PART NUMBER") "FDV303NDKR-ND")
        (field (name "07. MANUFACTURER  PART NUMBER") "FDV303N")
        (field (name "13. CREATED DATE/NAME") "AUG 2018 / Hören")
      )
      (libsource (lib "SCT8-Board1") (part "FDV303N"))
    )
    (comp (ref "Q38")
      (value "Q")
      (footprint "SOT23-3")
      (description "MOSFET N-CH 25V 680MA SOT-23")
      (fields
        (field (name "02. DISTRIBUTOR PART NUMBER") "FDV303NDKR-ND")
        (field (name "07. MANUFACTURER  PART NUMBER") "FDV303N")
        (field (name "13. CREATED DATE/NAME") "AUG 2018 / Hören")
      )
      (libsource (lib "SCT8-Board1") (part "FDV303N"))
    )
    (comp (ref "Q39")
      (value "Q")
      (footprint "SOT23-3")
      (description "MOSFET N-CH 25V 680MA SOT-23")
      (fields
        (field (name "02. DISTRIBUTOR PART NUMBER") "FDV303NDKR-ND")
        (field (name "07. MANUFACTURER  PART NUMBER") "FDV303N")
        (field (name "13. CREATED DATE/NAME") "AUG 2018 / Hören")
      )
      (libsource (lib "SCT8-Board1") (part "FDV303N"))
    )
    (comp (ref "Q40")
      (value "Q")
      (footprint "SOT23-3")
      (description "MOSFET N-CH 25V 680MA SOT-23")
      (fields
        (field (name "02. DISTRIBUTOR PART NUMBER") "FDV303NDKR-ND")
        (field (name "07. MANUFACTURER  PART NUMBER") "FDV303N")
        (field (name "13. CREATED DATE/NAME") "AUG 2018 / Hören")
      )
      (libsource (lib "SCT8-Board1") (part "FDV303N"))
    )
    (comp (ref "Q41")
      (value "Q")
      (footprint "SOT23-3")
      (description "MOSFET N-CH 25V 680MA SOT-23")
      (fields
        (field (name "02. DISTRIBUTOR PART NUMBER") "FDV303NDKR-ND")
        (field (name "07. MANUFACTURER  PART NUMBER") "FDV303N")
        (field (name "13. CREATED DATE/NAME") "AUG 2018 / Hören")
      )
      (libsource (lib "SCT8-Board1") (part "FDV303N"))
    )
    (comp (ref "Q42")
      (value "Q")
      (footprint "SOT23-3")
      (description "MOSFET N-CH 25V 680MA SOT-23")
      (fields
        (field (name "02. DISTRIBUTOR PART NUMBER") "FDV303NDKR-ND")
        (field (name "07. MANUFACTURER  PART NUMBER") "FDV303N")
        (field (name "13. CREATED DATE/NAME") "AUG 2018 / Hören")
      )
      (libsource (lib "SCT8-Board1") (part "FDV303N"))
    )
    (comp (ref "Q43")
      (value "Q")
      (footprint "SOT23-3")
      (description "MOSFET N-CH 25V 680MA SOT-23")
      (fields
        (field (name "02. DISTRIBUTOR PART NUMBER") "FDV303NDKR-ND")
        (field (name "07. MANUFACTURER  PART NUMBER") "FDV303N")
        (field (name "13. CREATED DATE/NAME") "AUG 2018 / Hören")
      )
      (libsource (lib "SCT8-Board1") (part "FDV303N"))
    )
    (comp (ref "Q44")
      (value "Q")
      (footprint "SOT23-3")
      (description "MOSFET N-CH 25V 680MA SOT-23")
      (fields
        (field (name "02. DISTRIBUTOR PART NUMBER") "FDV303NDKR-ND")
        (field (name "07. MANUFACTURER  PART NUMBER") "FDV303N")
        (field (name "13. CREATED DATE/NAME") "AUG 2018 / Hören")
      )
      (libsource (lib "SCT8-Board1") (part "FDV303N"))
    )
    (comp (ref "Q45")
      (value "Q")
      (footprint "SOT23-3")
      (description "MOSFET N-CH 25V 680MA SOT-23")
      (fields
        (field (name "02. DISTRIBUTOR PART NUMBER") "FDV303NDKR-ND")
        (field (name "07. MANUFACTURER  PART NUMBER") "FDV303N")
        (field (name "13. CREATED DATE/NAME") "AUG 2018 / Hören")
      )
      (libsource (lib "SCT8-Board1") (part "FDV303N"))
    )
    (comp (ref "Q46")
      (value "Q")
      (footprint "SOT23-3")
      (description "MOSFET N-CH 25V 680MA SOT-23")
      (fields
        (field (name "02. DISTRIBUTOR PART NUMBER") "FDV303NDKR-ND")
        (field (name "07. MANUFACTURER  PART NUMBER") "FDV303N")
        (field (name "13. CREATED DATE/NAME") "AUG 2018 / Hören")
      )
      (libsource (lib "SCT8-Board1") (part "FDV303N"))
    )
    (comp (ref "Q47")
      (value "Q")
      (footprint "SOT23-3")
      (description "MOSFET N-CH 25V 680MA SOT-23")
      (fields
        (field (name "02. DISTRIBUTOR PART NUMBER") "FDV303NDKR-ND")
        (field (name "07. MANUFACTURER  PART NUMBER") "FDV303N")
        (field (name "13. CREATED DATE/NAME") "AUG 2018 / Hören")
      )
      (libsource (lib "SCT8-Board1") (part "FDV303N"))
    )
    (comp (ref "Q48")
      (value "Q")
      (footprint "SOT23-3")
      (description "MOSFET N-CH 25V 680MA SOT-23")
      (fields
        (field (name "02. DISTRIBUTOR PART NUMBER") "FDV303NDKR-ND")
        (field (name "07. MANUFACTURER  PART NUMBER") "FDV303N")
        (field (name "13. CREATED DATE/NAME") "AUG 2018 / Hören")
      )
      (libsource (lib "SCT8-Board1") (part "FDV303N"))
    )
    (comp (ref "Q49")
      (value "Q")
      (footprint "SOT23-3")
      (description "MOSFET N-CH 25V 680MA SOT-23")
      (fields
        (field (name "02. DISTRIBUTOR PART NUMBER") "FDV303NDKR-ND")
        (field (name "07. MANUFACTURER  PART NUMBER") "FDV303N")
        (field (name "13. CREATED DATE/NAME") "AUG 2018 / Hören")
      )
      (libsource (lib "SCT8-Board1") (part "FDV303N"))
    )
    (comp (ref "Q50")
      (value "Q")
      (footprint "SOT23-3")
      (description "MOSFET N-CH 25V 680MA SOT-23")
      (fields
        (field (name "02. DISTRIBUTOR PART NUMBER") "FDV303NDKR-ND")
        (field (name "07. MANUFACTURER  PART NUMBER") "FDV303N")
        (field (name "13. CREATED DATE/NAME") "AUG 2018 / Hören")
      )
      (libsource (lib "SCT8-Board1") (part "FDV303N"))
    )
    (comp (ref "Q51")
      (value "Q")
      (footprint "SOT23-3")
      (description "MOSFET N-CH 25V 680MA SOT-23")
      (fields
        (field (name "02. DISTRIBUTOR PART NUMBER") "FDV303NDKR-ND")
        (field (name "07. MANUFACTURER  PART NUMBER") "FDV303N")
        (field (name "13. CREATED DATE/NAME") "AUG 2018 / Hören")
      )
      (libsource (lib "SCT8-Board1") (part "FDV303N"))
    )
    (comp (ref "Q52")
      (value "Q")
      (footprint "SOT23-3")
      (description "MOSFET N-CH 25V 680MA SOT-23")
      (fields
        (field (name "02. DISTRIBUTOR PART NUMBER") "FDV303NDKR-ND")
        (field (name "07. MANUFACTURER  PART NUMBER") "FDV303N")
        (field (name "13. CREATED DATE/NAME") "AUG 2018 / Hören")
      )
      (libsource (lib "SCT8-Board1") (part "FDV303N"))
    )
    (comp (ref "Q53")
      (value "Q")
      (footprint "SOT23-3")
      (description "MOSFET N-CH 25V 680MA SOT-23")
      (fields
        (field (name "02. DISTRIBUTOR PART NUMBER") "FDV303NDKR-ND")
        (field (name "07. MANUFACTURER  PART NUMBER") "FDV303N")
        (field (name "13. CREATED DATE/NAME") "AUG 2018 / Hören")
      )
      (libsource (lib "SCT8-Board1") (part "FDV303N"))
    )
    (comp (ref "Q54")
      (value "Q")
      (footprint "SOT23-3")
      (description "MOSFET N-CH 25V 680MA SOT-23")
      (fields
        (field (name "02. DISTRIBUTOR PART NUMBER") "FDV303NDKR-ND")
        (field (name "07. MANUFACTURER  PART NUMBER") "FDV303N")
        (field (name "13. CREATED DATE/NAME") "AUG 2018 / Hören")
      )
      (libsource (lib "SCT8-Board1") (part "FDV303N"))
    )
    (comp (ref "Q55")
      (value "Q")
      (footprint "SOT23-3")
      (description "MOSFET N-CH 25V 680MA SOT-23")
      (fields
        (field (name "02. DISTRIBUTOR PART NUMBER") "FDV303NDKR-ND")
        (field (name "07. MANUFACTURER  PART NUMBER") "FDV303N")
        (field (name "13. CREATED DATE/NAME") "AUG 2018 / Hören")
      )
      (libsource (lib "SCT8-Board1") (part "FDV303N"))
    )
    (comp (ref "Q56")
      (value "Q")
      (footprint "SOT23-3")
      (description "MOSFET N-CH 25V 680MA SOT-23")
      (fields
        (field (name "02. DISTRIBUTOR PART NUMBER") "FDV303NDKR-ND")
        (field (name "07. MANUFACTURER  PART NUMBER") "FDV303N")
        (field (name "13. CREATED DATE/NAME") "AUG 2018 / Hören")
      )
      (libsource (lib "SCT8-Board1") (part "FDV303N"))
    )
    (comp (ref "Q57")
      (value "Q")
      (footprint "SOT23-3")
      (description "MOSFET N-CH 25V 680MA SOT-23")
      (fields
        (field (name "02. DISTRIBUTOR PART NUMBER") "FDV303NDKR-ND")
        (field (name "07. MANUFACTURER  PART NUMBER") "FDV303N")
        (field (name "13. CREATED DATE/NAME") "AUG 2018 / Hören")
      )
      (libsource (lib "SCT8-Board1") (part "FDV303N"))
    )
    (comp (ref "Q58")
      (value "Q")
      (footprint "SOT23-3")
      (description "MOSFET N-CH 25V 680MA SOT-23")
      (fields
        (field (name "02. DISTRIBUTOR PART NUMBER") "FDV303NDKR-ND")
        (field (name "07. MANUFACTURER  PART NUMBER") "FDV303N")
        (field (name "13. CREATED DATE/NAME") "AUG 2018 / Hören")
      )
      (libsource (lib "SCT8-Board1") (part "FDV303N"))
    )
    (comp (ref "Q59")
      (value "Q")
      (footprint "SOT23-3")
      (description "MOSFET N-CH 25V 680MA SOT-23")
      (fields
        (field (name "02. DISTRIBUTOR PART NUMBER") "FDV303NDKR-ND")
        (field (name "07. MANUFACTURER  PART NUMBER") "FDV303N")
        (field (name "13. CREATED DATE/NAME") "AUG 2018 / Hören")
      )
      (libsource (lib "SCT8-Board1") (part "FDV303N"))
    )
    (comp (ref "Q60")
      (value "Q")
      (footprint "SOT23-3")
      (description "MOSFET N-CH 25V 680MA SOT-23")
      (fields
        (field (name "02. DISTRIBUTOR PART NUMBER") "FDV303NDKR-ND")
        (field (name "07. MANUFACTURER  PART NUMBER") "FDV303N")
        (field (name "13. CREATED DATE/NAME") "AUG 2018 / Hören")
      )
      (libsource (lib "SCT8-Board1") (part "FDV303N"))
    )
    (comp (ref "Q61")
      (value "Q")
      (footprint "SOT23-3")
      (description "MOSFET N-CH 25V 680MA SOT-23")
      (fields
        (field (name "02. DISTRIBUTOR PART NUMBER") "FDV303NDKR-ND")
        (field (name "07. MANUFACTURER  PART NUMBER") "FDV303N")
        (field (name "13. CREATED DATE/NAME") "AUG 2018 / Hören")
      )
      (libsource (lib "SCT8-Board1") (part "FDV303N"))
    )
    (comp (ref "Q62")
      (value "Q")
      (footprint "SOT23-3")
      (description "MOSFET N-CH 25V 680MA SOT-23")
      (fields
        (field (name "02. DISTRIBUTOR PART NUMBER") "FDV303NDKR-ND")
        (field (name "07. MANUFACTURER  PART NUMBER") "FDV303N")
        (field (name "13. CREATED DATE/NAME") "AUG 2018 / Hören")
      )
      (libsource (lib "SCT8-Board1") (part "FDV303N"))
    )
    (comp (ref "Q63")
      (value "Q")
      (footprint "SOT23-3")
      (description "MOSFET N-CH 25V 680MA SOT-23")
      (fields
        (field (name "02. DISTRIBUTOR PART NUMBER") "FDV303NDKR-ND")
        (field (name "07. MANUFACTURER  PART NUMBER") "FDV303N")
        (field (name "13. CREATED DATE/NAME") "AUG 2018 / Hören")
      )
      (libsource (lib "SCT8-Board1") (part "FDV303N"))
    )
    (comp (ref "Q64")
      (value "Q")
      (footprint "SOT23-3")
      (description "MOSFET N-CH 25V 680MA SOT-23")
      (fields
        (field (name "02. DISTRIBUTOR PART NUMBER") "FDV303NDKR-ND")
        (field (name "07. MANUFACTURER  PART NUMBER") "FDV303N")
        (field (name "13. CREATED DATE/NAME") "AUG 2018 / Hören")
      )
      (libsource (lib "SCT8-Board1") (part "FDV303N"))
    )
    (comp (ref "Q69")
      (value "Q")
      (footprint "SOT23-3")
      (description "MOSFET N-CH 25V 680MA SOT-23")
      (fields
        (field (name "02. DISTRIBUTOR PART NUMBER") "FDV303NDKR-ND")
        (field (name "07. MANUFACTURER  PART NUMBER") "FDV303N")
        (field (name "13. CREATED DATE/NAME") "AUG 2018 / Hören")
      )
      (libsource (lib "SCT8-Board1") (part "FDV303N"))
    )
    (comp (ref "R1")
      (value "4K7")
      (footprint "R0402 Reflow")
      (description "RES SMD 4.7K OHM 1% 1/16W 0402")
      (fields
        (field (name "TOLERANCE") "±1%")
        (field (name "02. DISTRIBUTOR PART NUMBER") "311-4.7KLRDKR-ND")
        (field (name "13. CREATED DATE/NAME") "AUG2018/Hören")
      )
      (libsource (lib "chickenfood") (part "R"))
    )
    (comp (ref "R2")
      (value "4K7")
      (footprint "R0402 Reflow")
      (description "RES SMD 4.7K OHM 1% 1/16W 0402")
      (fields
        (field (name "TOLERANCE") "±1%")
        (field (name "02. DISTRIBUTOR PART NUMBER") "311-4.7KLRDKR-ND")
        (field (name "13. CREATED DATE/NAME") "AUG2018/Hören")
      )
      (libsource (lib "chickenfood") (part "R"))
    )
    (comp (ref "R3")
      (value "4K7")
      (footprint "R0402 Reflow")
      (description "RES SMD 4.7K OHM 1% 1/16W 0402")
      (fields
        (field (name "TOLERANCE") "±1%")
        (field (name "02. DISTRIBUTOR PART NUMBER") "311-4.7KLRDKR-ND")
        (field (name "13. CREATED DATE/NAME") "AUG2018/Hören")
      )
      (libsource (lib "chickenfood") (part "R"))
    )
    (comp (ref "R4")
      (value "4K7")
      (footprint "R0402 Reflow")
      (description "RES SMD 4.7K OHM 1% 1/16W 0402")
      (fields
        (field (name "TOLERANCE") "±1%")
        (field (name "02. DISTRIBUTOR PART NUMBER") "311-4.7KLRDKR-ND")
        (field (name "13. CREATED DATE/NAME") "AUG2018/Hören")
      )
      (libsource (lib "chickenfood") (part "R"))
    )
    (comp (ref "R5")
      (value "4K7")
      (footprint "R0402 Reflow")
      (description "RES SMD 4.7K OHM 1% 1/16W 0402")
      (fields
        (field (name "TOLERANCE") "±1%")
        (field (name "02. DISTRIBUTOR PART NUMBER") "311-4.7KLRDKR-ND")
        (field (name "13. CREATED DATE/NAME") "AUG2018/Hören")
      )
      (libsource (lib "chickenfood") (part "R"))
    )
    (comp (ref "R6")
      (value "4K7")
      (footprint "R0402 Reflow")
      (description "RES SMD 4.7K OHM 1% 1/16W 0402")
      (fields
        (field (name "TOLERANCE") "±1%")
        (field (name "02. DISTRIBUTOR PART NUMBER") "311-4.7KLRDKR-ND")
        (field (name "13. CREATED DATE/NAME") "AUG2018/Hören")
      )
      (libsource (lib "chickenfood") (part "R"))
    )
    (comp (ref "R7")
      (value "4K7")
      (footprint "R0402 Reflow")
      (description "RES SMD 4.7K OHM 1% 1/16W 0402")
      (fields
        (field (name "TOLERANCE") "±1%")
        (field (name "02. DISTRIBUTOR PART NUMBER") "311-4.7KLRDKR-ND")
        (field (name "13. CREATED DATE/NAME") "AUG2018/Hören")
      )
      (libsource (lib "chickenfood") (part "R"))
    )
    (comp (ref "R8")
      (value "4K7")
      (footprint "R0402 Reflow")
      (description "RES SMD 4.7K OHM 1% 1/16W 0402")
      (fields
        (field (name "TOLERANCE") "±1%")
        (field (name "02. DISTRIBUTOR PART NUMBER") "311-4.7KLRDKR-ND")
        (field (name "13. CREATED DATE/NAME") "AUG2018/Hören")
      )
      (libsource (lib "chickenfood") (part "R"))
    )
    (comp (ref "R9")
      (value "4K7")
      (footprint "R0402 Reflow")
      (description "RES SMD 4.7K OHM 1% 1/16W 0402")
      (fields
        (field (name "TOLERANCE") "±1%")
        (field (name "02. DISTRIBUTOR PART NUMBER") "311-4.7KLRDKR-ND")
        (field (name "13. CREATED DATE/NAME") "AUG2018/Hören")
      )
      (libsource (lib "chickenfood") (part "R"))
    )
    (comp (ref "R10")
      (value "4K7")
      (footprint "R0402 Reflow")
      (description "RES SMD 4.7K OHM 1% 1/16W 0402")
      (fields
        (field (name "TOLERANCE") "±1%")
        (field (name "02. DISTRIBUTOR PART NUMBER") "311-4.7KLRDKR-ND")
        (field (name "13. CREATED DATE/NAME") "AUG2018/Hören")
      )
      (libsource (lib "chickenfood") (part "R"))
    )
    (comp (ref "R11")
      (value "4K7")
      (footprint "R0402 Reflow")
      (description "RES SMD 4.7K OHM 1% 1/16W 0402")
      (fields
        (field (name "TOLERANCE") "±1%")
        (field (name "02. DISTRIBUTOR PART NUMBER") "311-4.7KLRDKR-ND")
        (field (name "13. CREATED DATE/NAME") "AUG2018/Hören")
      )
      (libsource (lib "chickenfood") (part "R"))
    )
    (comp (ref "R12")
      (value "4K7")
      (footprint "R0402 Reflow")
      (description "RES SMD 4.7K OHM 1% 1/16W 0402")
      (fields
        (field (name "TOLERANCE") "±1%")
        (field (name "02. DISTRIBUTOR PART NUMBER") "311-4.7KLRDKR-ND")
        (field (name "13. CREATED DATE/NAME") "AUG2018/Hören")
      )
      (libsource (lib "chickenfood") (part "R"))
    )
    (comp (ref "R13")
      (value "4K7")
      (footprint "R0402 Reflow")
      (description "RES SMD 4.7K OHM 1% 1/16W 0402")
      (fields
        (field (name "TOLERANCE") "±1%")
        (field (name "02. DISTRIBUTOR PART NUMBER") "311-4.7KLRDKR-ND")
        (field (name "13. CREATED DATE/NAME") "AUG2018/Hören")
      )
      (libsource (lib "chickenfood") (part "R"))
    )
    (comp (ref "R14")
      (value "4K7")
      (footprint "R0402 Reflow")
      (description "RES SMD 4.7K OHM 1% 1/16W 0402")
      (fields
        (field (name "TOLERANCE") "±1%")
        (field (name "02. DISTRIBUTOR PART NUMBER") "311-4.7KLRDKR-ND")
        (field (name "13. CREATED DATE/NAME") "AUG2018/Hören")
      )
      (libsource (lib "chickenfood") (part "R"))
    )
    (comp (ref "R15")
      (value "4K7")
      (footprint "R0402 Reflow")
      (description "RES SMD 4.7K OHM 1% 1/16W 0402")
      (fields
        (field (name "TOLERANCE") "±1%")
        (field (name "02. DISTRIBUTOR PART NUMBER") "311-4.7KLRDKR-ND")
        (field (name "13. CREATED DATE/NAME") "AUG2018/Hören")
      )
      (libsource (lib "chickenfood") (part "R"))
    )
    (comp (ref "R16")
      (value "4K7")
      (footprint "R0402 Reflow")
      (description "RES SMD 4.7K OHM 1% 1/16W 0402")
      (fields
        (field (name "TOLERANCE") "±1%")
        (field (name "02. DISTRIBUTOR PART NUMBER") "311-4.7KLRDKR-ND")
        (field (name "13. CREATED DATE/NAME") "AUG2018/Hören")
      )
      (libsource (lib "chickenfood") (part "R"))
    )
    (comp (ref "R17")
      (value "4K7")
      (footprint "R0402 Reflow")
      (description "RES SMD 4.7K OHM 1% 1/16W 0402")
      (fields
        (field (name "TOLERANCE") "±1%")
        (field (name "02. DISTRIBUTOR PART NUMBER") "311-4.7KLRDKR-ND")
        (field (name "13. CREATED DATE/NAME") "AUG2018/Hören")
      )
      (libsource (lib "chickenfood") (part "R"))
    )
    (comp (ref "R18")
      (value "4K7")
      (footprint "R0402 Reflow")
      (description "RES SMD 4.7K OHM 1% 1/16W 0402")
      (fields
        (field (name "TOLERANCE") "±1%")
        (field (name "02. DISTRIBUTOR PART NUMBER") "311-4.7KLRDKR-ND")
        (field (name "13. CREATED DATE/NAME") "AUG2018/Hören")
      )
      (libsource (lib "chickenfood") (part "R"))
    )
    (comp (ref "R19")
      (value "4K7")
      (footprint "R0402 Reflow")
      (description "RES SMD 4.7K OHM 1% 1/16W 0402")
      (fields
        (field (name "TOLERANCE") "±1%")
        (field (name "02. DISTRIBUTOR PART NUMBER") "311-4.7KLRDKR-ND")
        (field (name "13. CREATED DATE/NAME") "AUG2018/Hören")
      )
      (libsource (lib "chickenfood") (part "R"))
    )
    (comp (ref "R20")
      (value "4K7")
      (footprint "R0402 Reflow")
      (description "RES SMD 4.7K OHM 1% 1/16W 0402")
      (fields
        (field (name "TOLERANCE") "±1%")
        (field (name "02. DISTRIBUTOR PART NUMBER") "311-4.7KLRDKR-ND")
        (field (name "13. CREATED DATE/NAME") "AUG2018/Hören")
      )
      (libsource (lib "chickenfood") (part "R"))
    )
    (comp (ref "R21")
      (value "4K7")
      (footprint "R0402 Reflow")
      (description "RES SMD 4.7K OHM 1% 1/16W 0402")
      (fields
        (field (name "TOLERANCE") "±1%")
        (field (name "02. DISTRIBUTOR PART NUMBER") "311-4.7KLRDKR-ND")
        (field (name "13. CREATED DATE/NAME") "AUG2018/Hören")
      )
      (libsource (lib "chickenfood") (part "R"))
    )
    (comp (ref "R22")
      (value "4K7")
      (footprint "R0402 Reflow")
      (description "RES SMD 4.7K OHM 1% 1/16W 0402")
      (fields
        (field (name "TOLERANCE") "±1%")
        (field (name "02. DISTRIBUTOR PART NUMBER") "311-4.7KLRDKR-ND")
        (field (name "13. CREATED DATE/NAME") "AUG2018/Hören")
      )
      (libsource (lib "chickenfood") (part "R"))
    )
    (comp (ref "R23")
      (value "4K7")
      (footprint "R0402 Reflow")
      (description "RES SMD 4.7K OHM 1% 1/16W 0402")
      (fields
        (field (name "TOLERANCE") "±1%")
        (field (name "02. DISTRIBUTOR PART NUMBER") "311-4.7KLRDKR-ND")
        (field (name "13. CREATED DATE/NAME") "AUG2018/Hören")
      )
      (libsource (lib "chickenfood") (part "R"))
    )
    (comp (ref "R24")
      (value "4K7")
      (footprint "R0402 Reflow")
      (description "RES SMD 4.7K OHM 1% 1/16W 0402")
      (fields
        (field (name "TOLERANCE") "±1%")
        (field (name "02. DISTRIBUTOR PART NUMBER") "311-4.7KLRDKR-ND")
        (field (name "13. CREATED DATE/NAME") "AUG2018/Hören")
      )
      (libsource (lib "chickenfood") (part "R"))
    )
    (comp (ref "R25")
      (value "4K7")
      (footprint "R0402 Reflow")
      (description "RES SMD 4.7K OHM 1% 1/16W 0402")
      (fields
        (field (name "TOLERANCE") "±1%")
        (field (name "02. DISTRIBUTOR PART NUMBER") "311-4.7KLRDKR-ND")
        (field (name "13. CREATED DATE/NAME") "AUG2018/Hören")
      )
      (libsource (lib "chickenfood") (part "R"))
    )
    (comp (ref "R26")
      (value "4K7")
      (footprint "R0402 Reflow")
      (description "RES SMD 4.7K OHM 1% 1/16W 0402")
      (fields
        (field (name "TOLERANCE") "±1%")
        (field (name "02. DISTRIBUTOR PART NUMBER") "311-4.7KLRDKR-ND")
        (field (name "13. CREATED DATE/NAME") "AUG2018/Hören")
      )
      (libsource (lib "chickenfood") (part "R"))
    )
    (comp (ref "R27")
      (value "4K7")
      (footprint "R0402 Reflow")
      (description "RES SMD 4.7K OHM 1% 1/16W 0402")
      (fields
        (field (name "TOLERANCE") "±1%")
        (field (name "02. DISTRIBUTOR PART NUMBER") "311-4.7KLRDKR-ND")
        (field (name "13. CREATED DATE/NAME") "AUG2018/Hören")
      )
      (libsource (lib "chickenfood") (part "R"))
    )
    (comp (ref "R28")
      (value "4K7")
      (footprint "R0402 Reflow")
      (description "RES SMD 4.7K OHM 1% 1/16W 0402")
      (fields
        (field (name "TOLERANCE") "±1%")
        (field (name "02. DISTRIBUTOR PART NUMBER") "311-4.7KLRDKR-ND")
        (field (name "13. CREATED DATE/NAME") "AUG2018/Hören")
      )
      (libsource (lib "chickenfood") (part "R"))
    )
    (comp (ref "R29")
      (value "4K7")
      (footprint "R0402 Reflow")
      (description "RES SMD 4.7K OHM 1% 1/16W 0402")
      (fields
        (field (name "TOLERANCE") "±1%")
        (field (name "02. DISTRIBUTOR PART NUMBER") "311-4.7KLRDKR-ND")
        (field (name "13. CREATED DATE/NAME") "AUG2018/Hören")
      )
      (libsource (lib "chickenfood") (part "R"))
    )
    (comp (ref "R30")
      (value "4K7")
      (footprint "R0402 Reflow")
      (description "RES SMD 4.7K OHM 1% 1/16W 0402")
      (fields
        (field (name "TOLERANCE") "±1%")
        (field (name "02. DISTRIBUTOR PART NUMBER") "311-4.7KLRDKR-ND")
        (field (name "13. CREATED DATE/NAME") "AUG2018/Hören")
      )
      (libsource (lib "chickenfood") (part "R"))
    )
    (comp (ref "R31")
      (value "4K7")
      (footprint "R0402 Reflow")
      (description "RES SMD 4.7K OHM 1% 1/16W 0402")
      (fields
        (field (name "TOLERANCE") "±1%")
        (field (name "02. DISTRIBUTOR PART NUMBER") "311-4.7KLRDKR-ND")
        (field (name "13. CREATED DATE/NAME") "AUG2018/Hören")
      )
      (libsource (lib "chickenfood") (part "R"))
    )
    (comp (ref "R32")
      (value "4K7")
      (footprint "R0402 Reflow")
      (description "RES SMD 4.7K OHM 1% 1/16W 0402")
      (fields
        (field (name "TOLERANCE") "±1%")
        (field (name "02. DISTRIBUTOR PART NUMBER") "311-4.7KLRDKR-ND")
        (field (name "13. CREATED DATE/NAME") "AUG2018/Hören")
      )
      (libsource (lib "chickenfood") (part "R"))
    )
    (comp (ref "R33")
      (value "4K7")
      (footprint "R0402 Reflow")
      (description "RES SMD 4.7K OHM 1% 1/16W 0402")
      (fields
        (field (name "TOLERANCE") "±1%")
        (field (name "02. DISTRIBUTOR PART NUMBER") "311-4.7KLRDKR-ND")
        (field (name "13. CREATED DATE/NAME") "AUG2018/Hören")
      )
      (libsource (lib "chickenfood") (part "R"))
    )
    (comp (ref "R34")
      (value "4K7")
      (footprint "R0402 Reflow")
      (description "RES SMD 4.7K OHM 1% 1/16W 0402")
      (fields
        (field (name "TOLERANCE") "±1%")
        (field (name "02. DISTRIBUTOR PART NUMBER") "311-4.7KLRDKR-ND")
        (field (name "13. CREATED DATE/NAME") "AUG2018/Hören")
      )
      (libsource (lib "chickenfood") (part "R"))
    )
    (comp (ref "R35")
      (value "4K7")
      (footprint "R0402 Reflow")
      (description "RES SMD 4.7K OHM 1% 1/16W 0402")
      (fields
        (field (name "TOLERANCE") "±1%")
        (field (name "02. DISTRIBUTOR PART NUMBER") "311-4.7KLRDKR-ND")
        (field (name "13. CREATED DATE/NAME") "AUG2018/Hören")
      )
      (libsource (lib "chickenfood") (part "R"))
    )
    (comp (ref "R36")
      (value "4K7")
      (footprint "R0402 Reflow")
      (description "RES SMD 4.7K OHM 1% 1/16W 0402")
      (fields
        (field (name "TOLERANCE") "±1%")
        (field (name "02. DISTRIBUTOR PART NUMBER") "311-4.7KLRDKR-ND")
        (field (name "13. CREATED DATE/NAME") "AUG2018/Hören")
      )
      (libsource (lib "chickenfood") (part "R"))
    )
    (comp (ref "R37")
      (value "4K7")
      (footprint "R0402 Reflow")
      (description "RES SMD 4.7K OHM 1% 1/16W 0402")
      (fields
        (field (name "TOLERANCE") "±1%")
        (field (name "02. DISTRIBUTOR PART NUMBER") "311-4.7KLRDKR-ND")
        (field (name "13. CREATED DATE/NAME") "AUG2018/Hören")
      )
      (libsource (lib "chickenfood") (part "R"))
    )
    (comp (ref "R38")
      (value "4K7")
      (footprint "R0402 Reflow")
      (description "RES SMD 4.7K OHM 1% 1/16W 0402")
      (fields
        (field (name "TOLERANCE") "±1%")
        (field (name "02. DISTRIBUTOR PART NUMBER") "311-4.7KLRDKR-ND")
        (field (name "13. CREATED DATE/NAME") "AUG2018/Hören")
      )
      (libsource (lib "chickenfood") (part "R"))
    )
    (comp (ref "R39")
      (value "4K7")
      (footprint "R0402 Reflow")
      (description "RES SMD 4.7K OHM 1% 1/16W 0402")
      (fields
        (field (name "TOLERANCE") "±1%")
        (field (name "02. DISTRIBUTOR PART NUMBER") "311-4.7KLRDKR-ND")
        (field (name "13. CREATED DATE/NAME") "AUG2018/Hören")
      )
      (libsource (lib "chickenfood") (part "R"))
    )
    (comp (ref "R40")
      (value "4K7")
      (footprint "R0402 Reflow")
      (description "RES SMD 4.7K OHM 1% 1/16W 0402")
      (fields
        (field (name "TOLERANCE") "±1%")
        (field (name "02. DISTRIBUTOR PART NUMBER") "311-4.7KLRDKR-ND")
        (field (name "13. CREATED DATE/NAME") "AUG2018/Hören")
      )
      (libsource (lib "chickenfood") (part "R"))
    )
    (comp (ref "R41")
      (value "4K7")
      (footprint "R0402 Reflow")
      (description "RES SMD 4.7K OHM 1% 1/16W 0402")
      (fields
        (field (name "TOLERANCE") "±1%")
        (field (name "02. DISTRIBUTOR PART NUMBER") "311-4.7KLRDKR-ND")
        (field (name "13. CREATED DATE/NAME") "AUG2018/Hören")
      )
      (libsource (lib "chickenfood") (part "R"))
    )
    (comp (ref "R42")
      (value "4K7")
      (footprint "R0402 Reflow")
      (description "RES SMD 4.7K OHM 1% 1/16W 0402")
      (fields
        (field (name "TOLERANCE") "±1%")
        (field (name "02. DISTRIBUTOR PART NUMBER") "311-4.7KLRDKR-ND")
        (field (name "13. CREATED DATE/NAME") "AUG2018/Hören")
      )
      (libsource (lib "chickenfood") (part "R"))
    )
    (comp (ref "R48")
      (value "4K7")
      (footprint "R0402 Reflow")
      (description "RES SMD 4.7K OHM 1% 1/16W 0402")
      (fields
        (field (name "TOLERANCE") "±1%")
        (field (name "02. DISTRIBUTOR PART NUMBER") "311-4.7KLRDKR-ND")
        (field (name "13. CREATED DATE/NAME") "AUG2018/Hören")
      )
      (libsource (lib "chickenfood") (part "R"))
    )
    (comp (ref "R49")
      (value "4K7")
      (footprint "R0402 Reflow")
      (description "RES SMD 4.7K OHM 1% 1/16W 0402")
      (fields
        (field (name "TOLERANCE") "±1%")
        (field (name "02. DISTRIBUTOR PART NUMBER") "311-4.7KLRDKR-ND")
        (field (name "13. CREATED DATE/NAME") "AUG2018/Hören")
      )
      (libsource (lib "chickenfood") (part "R"))
    )
    (comp (ref "R50")
      (value "4K7")
      (footprint "R0402 Reflow")
      (description "RES SMD 4.7K OHM 1% 1/16W 0402")
      (fields
        (field (name "TOLERANCE") "±1%")
        (field (name "02. DISTRIBUTOR PART NUMBER") "311-4.7KLRDKR-ND")
        (field (name "13. CREATED DATE/NAME") "AUG2018/Hören")
      )
      (libsource (lib "chickenfood") (part "R"))
    )
    (comp (ref "R51")
      (value "4K7")
      (footprint "R0402 Reflow")
      (description "RES SMD 4.7K OHM 1% 1/16W 0402")
      (fields
        (field (name "TOLERANCE") "±1%")
        (field (name "02. DISTRIBUTOR PART NUMBER") "311-4.7KLRDKR-ND")
        (field (name "13. CREATED DATE/NAME") "AUG2018/Hören")
      )
      (libsource (lib "chickenfood") (part "R"))
    )
    (comp (ref "R52")
      (value "4K7")
      (footprint "R0402 Reflow")
      (description "RES SMD 4.7K OHM 1% 1/16W 0402")
      (fields
        (field (name "TOLERANCE") "±1%")
        (field (name "02. DISTRIBUTOR PART NUMBER") "311-4.7KLRDKR-ND")
        (field (name "13. CREATED DATE/NAME") "AUG2018/Hören")
      )
      (libsource (lib "chickenfood") (part "R"))
    )
    (comp (ref "R53")
      (value "4K7")
      (footprint "R0402 Reflow")
      (description "RES SMD 4.7K OHM 1% 1/16W 0402")
      (fields
        (field (name "TOLERANCE") "±1%")
        (field (name "02. DISTRIBUTOR PART NUMBER") "311-4.7KLRDKR-ND")
        (field (name "13. CREATED DATE/NAME") "AUG2018/Hören")
      )
      (libsource (lib "chickenfood") (part "R"))
    )
    (comp (ref "R54")
      (value "4K7")
      (footprint "R0402 Reflow")
      (description "RES SMD 4.7K OHM 1% 1/16W 0402")
      (fields
        (field (name "TOLERANCE") "±1%")
        (field (name "02. DISTRIBUTOR PART NUMBER") "311-4.7KLRDKR-ND")
        (field (name "13. CREATED DATE/NAME") "AUG2018/Hören")
      )
      (libsource (lib "chickenfood") (part "R"))
    )
    (comp (ref "R55")
      (value "4K7")
      (footprint "R0402 Reflow")
      (description "RES SMD 4.7K OHM 1% 1/16W 0402")
      (fields
        (field (name "TOLERANCE") "±1%")
        (field (name "02. DISTRIBUTOR PART NUMBER") "311-4.7KLRDKR-ND")
        (field (name "13. CREATED DATE/NAME") "AUG2018/Hören")
      )
      (libsource (lib "chickenfood") (part "R"))
    )
    (comp (ref "R56")
      (value "4K7")
      (footprint "R0402 Reflow")
      (description "RES SMD 4.7K OHM 1% 1/16W 0402")
      (fields
        (field (name "TOLERANCE") "±1%")
        (field (name "02. DISTRIBUTOR PART NUMBER") "311-4.7KLRDKR-ND")
        (field (name "13. CREATED DATE/NAME") "AUG2018/Hören")
      )
      (libsource (lib "chickenfood") (part "R"))
    )
    (comp (ref "R57")
      (value "4K7")
      (footprint "R0402 Reflow")
      (description "RES SMD 4.7K OHM 1% 1/16W 0402")
      (fields
        (field (name "TOLERANCE") "±1%")
        (field (name "02. DISTRIBUTOR PART NUMBER") "311-4.7KLRDKR-ND")
        (field (name "13. CREATED DATE/NAME") "AUG2018/Hören")
      )
      (libsource (lib "chickenfood") (part "R"))
    )
    (comp (ref "R58")
      (value "4K7")
      (footprint "R0402 Reflow")
      (description "RES SMD 4.7K OHM 1% 1/16W 0402")
      (fields
        (field (name "TOLERANCE") "±1%")
        (field (name "02. DISTRIBUTOR PART NUMBER") "311-4.7KLRDKR-ND")
        (field (name "13. CREATED DATE/NAME") "AUG2018/Hören")
      )
      (libsource (lib "chickenfood") (part "R"))
    )
    (comp (ref "R59")
      (value "4K7")
      (footprint "R0402 Reflow")
      (description "RES SMD 4.7K OHM 1% 1/16W 0402")
      (fields
        (field (name "TOLERANCE") "±1%")
        (field (name "02. DISTRIBUTOR PART NUMBER") "311-4.7KLRDKR-ND")
        (field (name "13. CREATED DATE/NAME") "AUG2018/Hören")
      )
      (libsource (lib "chickenfood") (part "R"))
    )
    (comp (ref "R60")
      (value "4K7")
      (footprint "R0402 Reflow")
      (description "RES SMD 4.7K OHM 1% 1/16W 0402")
      (fields
        (field (name "TOLERANCE") "±1%")
        (field (name "02. DISTRIBUTOR PART NUMBER") "311-4.7KLRDKR-ND")
        (field (name "13. CREATED DATE/NAME") "AUG2018/Hören")
      )
      (libsource (lib "chickenfood") (part "R"))
    )
    (comp (ref "R61")
      (value "4K7")
      (footprint "R0402 Reflow")
      (description "RES SMD 4.7K OHM 1% 1/16W 0402")
      (fields
        (field (name "TOLERANCE") "±1%")
        (field (name "02. DISTRIBUTOR PART NUMBER") "311-4.7KLRDKR-ND")
        (field (name "13. CREATED DATE/NAME") "AUG2018/Hören")
      )
      (libsource (lib "chickenfood") (part "R"))
    )
    (comp (ref "R62")
      (value "4K7")
      (footprint "R0402 Reflow")
      (description "RES SMD 4.7K OHM 1% 1/16W 0402")
      (fields
        (field (name "TOLERANCE") "±1%")
        (field (name "02. DISTRIBUTOR PART NUMBER") "311-4.7KLRDKR-ND")
        (field (name "13. CREATED DATE/NAME") "AUG2018/Hören")
      )
      (libsource (lib "chickenfood") (part "R"))
    )
    (comp (ref "R63")
      (value "4K7")
      (footprint "R0402 Reflow")
      (description "RES SMD 4.7K OHM 1% 1/16W 0402")
      (fields
        (field (name "TOLERANCE") "±1%")
        (field (name "02. DISTRIBUTOR PART NUMBER") "311-4.7KLRDKR-ND")
        (field (name "13. CREATED DATE/NAME") "AUG2018/Hören")
      )
      (libsource (lib "chickenfood") (part "R"))
    )
    (comp (ref "R64")
      (value "4K7")
      (footprint "R0402 Reflow")
      (description "RES SMD 4.7K OHM 1% 1/16W 0402")
      (fields
        (field (name "TOLERANCE") "±1%")
        (field (name "02. DISTRIBUTOR PART NUMBER") "311-4.7KLRDKR-ND")
        (field (name "13. CREATED DATE/NAME") "AUG2018/Hören")
      )
      (libsource (lib "chickenfood") (part "R"))
    )
    (comp (ref "R65")
      (value "4K7")
      (footprint "R0402 Reflow")
      (description "RES SMD 4.7K OHM 1% 1/16W 0402")
      (fields
        (field (name "TOLERANCE") "±1%")
        (field (name "02. DISTRIBUTOR PART NUMBER") "311-4.7KLRDKR-ND")
        (field (name "13. CREATED DATE/NAME") "AUG2018/Hören")
      )
      (libsource (lib "chickenfood") (part "R"))
    )
    (comp (ref "R66")
      (value "4K7")
      (footprint "R0402 Reflow")
      (description "RES SMD 4.7K OHM 1% 1/16W 0402")
      (fields
        (field (name "TOLERANCE") "±1%")
        (field (name "02. DISTRIBUTOR PART NUMBER") "311-4.7KLRDKR-ND")
        (field (name "13. CREATED DATE/NAME") "AUG2018/Hören")
      )
      (libsource (lib "chickenfood") (part "R"))
    )
    (comp (ref "R67")
      (value "4K7")
      (footprint "R0402 Reflow")
      (description "RES SMD 4.7K OHM 1% 1/16W 0402")
      (fields
        (field (name "TOLERANCE") "±1%")
        (field (name "02. DISTRIBUTOR PART NUMBER") "311-4.7KLRDKR-ND")
        (field (name "13. CREATED DATE/NAME") "AUG2018/Hören")
      )
      (libsource (lib "chickenfood") (part "R"))
    )
    (comp (ref "R68")
      (value "4K7")
      (footprint "R0402 Reflow")
      (description "RES SMD 4.7K OHM 1% 1/16W 0402")
      (fields
        (field (name "TOLERANCE") "±1%")
        (field (name "02. DISTRIBUTOR PART NUMBER") "311-4.7KLRDKR-ND")
        (field (name "13. CREATED DATE/NAME") "AUG2018/Hören")
      )
      (libsource (lib "chickenfood") (part "R"))
    )
    (comp (ref "R69")
      (value "4K7")
      (footprint "R0402 Reflow")
      (description "RES SMD 4.7K OHM 1% 1/16W 0402")
      (fields
        (field (name "TOLERANCE") "±1%")
        (field (name "02. DISTRIBUTOR PART NUMBER") "311-4.7KLRDKR-ND")
        (field (name "13. CREATED DATE/NAME") "AUG2018/Hören")
      )
      (libsource (lib "chickenfood") (part "R"))
    )
    (comp (ref "R121")
      (value "10k")
      (footprint "R0402 Reflow")
      (description "RES SMD 10K OHM 1% 1/16W 0402")
      (fields
        (field (name "TOLERANCE") "±1%")
        (field (name "02. DISTRIBUTOR PART NUMBER") "311-10.0KLRDKR-ND")
        (field (name "13. CREATED DATE/NAME") "AUG2018/Hören")
      )
      (libsource (lib "chickenfood") (part "R"))
    )
    (comp (ref "R125")
      (value "3k6")
      (footprint "R0603 Reflow")
      (description "RES SMD 3.6K OHM 1% 1/10W 0603")
      (fields
        (field (name "TOLERANCE") "±1%")
        (field (name "02. DISTRIBUTOR PART NUMBER") "311-3.60KHRCT-ND")
        (field (name "13. CREATED DATE/NAME") "AUG2018/Hören")
      )
      (libsource (lib "chickenfood") (part "R"))
    )
    (comp (ref "R130")
      (value "4K7")
      (footprint "R0402 Reflow")
      (description "RES SMD 4.7K OHM 1% 1/16W 0402")
      (fields
        (field (name "TOLERANCE") "±1%")
        (field (name "02. DISTRIBUTOR PART NUMBER") "311-4.7KLRDKR-ND")
        (field (name "13. CREATED DATE/NAME") "AUG2018/Hören")
      )
      (libsource (lib "chickenfood") (part "R"))
    )
    (comp (ref "TP5")
      (value "TP")
      (footprint "DualTestpoint 100mils")
      (description "Dual testpoint, pitch 2.54mm")
      (fields
        (field (name "02. DISTRIBUTOR PART NUMBER") "HMTSW-103-07-G-S-240")
        (field (name "13. CREATED DATE/NAME") "AUG2018/Hören")
      )
      (libsource (lib "PCB-Tester-Board-V1") (part "DualTestpoint 100mils"))
    )
    (comp (ref "TP6")
      (value "TP")
      (footprint "DualTestpoint 100mils")
      (description "Dual testpoint, pitch 2.54mm")
      (fields
        (field (name "02. DISTRIBUTOR PART NUMBER") "HMTSW-103-07-G-S-240")
        (field (name "13. CREATED DATE/NAME") "AUG2018/Hören")
      )
      (libsource (lib "PCB-Tester-Board-V1") (part "DualTestpoint 100mils"))
    )
    (comp (ref "X1")
      (value "X")
      (description "32 x 2 x 1.27mm SOCKET DISCRETE CABL COLORED")
      (fields
        (field (name "02. DISTRIBUTOR PART NUMBER") "SFSD-32-30C-G-15.00-S")
        (field (name "13. CREATED DATE/NAME") "??? / Hören")
      )
      (libsource (lib "PCB-Relay-Board-V1") (part "SFSD-32-30C-G-15.00-S"))
    )
    (comp (ref "X2")
      (value "X")
      (footprint "TFC-132-01-F-D-RA")
      (description "CONN HEADER TH RA 48POS 1.27MM")
      (fields
        (field (name "02. DISTRIBUTOR PART NUMBER") "TFC-132-01-F-D-RA")
        (field (name "13. CREATED DATE/NAME") "??? / Hören")
      )
      (libsource (lib "PCB-Relay-Board-V1") (part "TFC-132-01-F-D-RA"))
    )
    (comp (ref "X3")
      (value "X")
      (footprint "CONFIG64")
      (description "PCB Tester Configuration Matrix for 48 Relays over 8 ABUSes")
      (fields (field (name "13. CREATED DATE/NAME") "??? / Hören"))
      (libsource (lib "PCB-Relay-Board-V1") (part "CONFIG64"))
    )
    (comp (ref "X4")
      (value "X")
      (footprint "PCIE-036-02-F-D-Fingers")
      (description "CONN PCI Card Edge 36POS")
      (libsource (lib "Connectors") (part "PCIE-036-02-F-D-Fingers"))
    )
  )
  (nets
    (net (code "4") (name "/A0") (class "Default")
      (node (ref "X4") (pin "B18") (pinfunction "B18_B18") (pintype "passive"))
    )
    (net (code "5") (name "/A1") (class "Default")
      (node (ref "X4") (pin "A18") (pinfunction "A18_A18") (pintype "passive"))
    )
    (net (code "6") (name "/A2") (class "Default")
      (node (ref "X4") (pin "B17") (pinfunction "B17_B17") (pintype "passive"))
    )
    (net (code "7") (name "/A3") (class "Default")
      (node (ref "X4") (pin "A17") (pinfunction "A17_A17") (pintype "passive"))
    )
    (net (code "8") (name "/ABUS0") (class "Default")
      (node (ref "X3") (pin "ABUS0") (pinfunction "ABUS0_ABUS0") (pintype "passive"))
      (node (ref "X4") (pin "A5") (pinfunction "A5_A5") (pintype "passive"))
    )
    (net (code "9") (name "/ABUS1") (class "Default")
      (node (ref "X3") (pin "ABUS1") (pinfunction "ABUS1_ABUS1") (pintype "passive"))
      (node (ref "X4") (pin "B5") (pinfunction "B5_B5") (pintype "passive"))
    )
    (net (code "10") (name "/ABUS2") (class "Default")
      (node (ref "X3") (pin "ABUS2") (pinfunction "ABUS2_ABUS2") (pintype "passive"))
      (node (ref "X4") (pin "A4") (pinfunction "A4_A4") (pintype "passive"))
    )
    (net (code "11") (name "/ABUS3") (class "Default")
      (node (ref "X3") (pin "ABUS3") (pinfunction "ABUS3_ABUS3") (pintype "passive"))
      (node (ref "X4") (pin "B4") (pinfunction "B4_B4") (pintype "passive"))
    )
    (net (code "12") (name "/ABUS4") (class "Default")
      (node (ref "X3") (pin "ABUS4") (pinfunction "ABUS4_ABUS4") (pintype "passive"))
      (node (ref "X4") (pin "A3") (pinfunction "A3_A3") (pintype "passive"))
    )
    (net (code "13") (name "/ABUS5") (class "Default")
      (node (ref "X3") (pin "ABUS5") (pinfunction "ABUS5_ABUS5") (pintype "passive"))
      (node (ref "X4") (pin "B3") (pinfunction "B3_B3") (pintype "passive"))
    )
    (net (code "14") (name "/ABUS6") (class "Default")
      (node (ref "X3") (pin "ABUS6") (pinfunction "ABUS6_ABUS6") (pintype "passive"))
      (node (ref "X4") (pin "A2") (pinfunction "A2_A2") (pintype "passive"))
    )
    (net (code "15") (name "/ABUS7") (class "Default")
      (node (ref "X3") (pin "ABUS7") (pinfunction "ABUS7_ABUS7") (pintype "passive"))
      (node (ref "X4") (pin "B2") (pinfunction "B2_B2") (pintype "passive"))
    )
    (net (code "17") (name "/ALERT#") (class "Default")
      (node (ref "J11") (pin "5") (pinfunction "5_5") (pintype "passive"))
    )
    (net (code "18") (name "/CLK") (class "Default")
      (node (ref "J11") (pin "7") (pinfunction "7_7") (pintype "passive"))
    )
    (net (code "19") (name "/CS") (class "Default")
      (node (ref "R121") (pin "1") (pinfunction "1_1") (pintype "passive"))
      (node (ref "X4") (pin "B15") (pinfunction "B15_B15") (pintype "passive"))
    )
    (net (code "20") (name "/DATA") (class "Default")
      (node (ref "J11") (pin "9") (pinfunction "9_9") (pintype "passive"))
    )
    (net (code "21") (name "/DRV1") (class "Default")
      (node (ref "Q1") (pin "1") (pinfunction "G_1") (pintype "passive"))
      (node (ref "R1") (pin "2") (pinfunction "2_2") (pintype "passive"))
    )
    (net (code "22") (name "/DRV2") (class "Default")
      (node (ref "Q2") (pin "1") (pinfunction "G_1") (pintype "passive"))
      (node (ref "R2") (pin "2") (pinfunction "2_2") (pintype "passive"))
    )
    (net (code "23") (name "/DRV3") (class "Default")
      (node (ref "Q3") (pin "1") (pinfunction "G_1") (pintype "passive"))
      (node (ref "R3") (pin "2") (pinfunction "2_2") (pintype "passive"))
    )
    (net (code "24") (name "/DRV4") (class "Default")
      (node (ref "Q4") (pin "1") (pinfunction "G_1") (pintype "passive"))
      (node (ref "R4") (pin "2") (pinfunction "2_2") (pintype "passive"))
    )
    (net (code "25") (name "/DRV5") (class "Default")
      (node (ref "Q5") (pin "1") (pinfunction "G_1") (pintype "passive"))
      (node (ref "R5") (pin "2") (pinfunction "2_2") (pintype "passive"))
    )
    (net (code "26") (name "/DRV6") (class "Default")
      (node (ref "Q6") (pin "1") (pinfunction "G_1") (pintype "passive"))
      (node (ref "R6") (pin "2") (pinfunction "2_2") (pintype "passive"))
    )
    (net (code "27") (name "/DRV7") (class "Default")
      (node (ref "Q7") (pin "1") (pinfunction "G_1") (pintype "passive"))
      (node (ref "R7") (pin "2") (pinfunction "2_2") (pintype "passive"))
    )
    (net (code "28") (name "/DRV8") (class "Default")
      (node (ref "Q8") (pin "1") (pinfunction "G_1") (pintype "passive"))
      (node (ref "R8") (pin "2") (pinfunction "2_2") (pintype "passive"))
    )
    (net (code "29") (name "/DRV9") (class "Default")
      (node (ref "Q9") (pin "1") (pinfunction "G_1") (pintype "passive"))
      (node (ref "R9") (pin "2") (pinfunction "2_2") (pintype "passive"))
    )
    (net (code "30") (name "/DRV10") (class "Default")
      (node (ref "Q10") (pin "1") (pinfunction "G_1") (pintype "passive"))
      (node (ref "R10") (pin "2") (pinfunction "2_2") (pintype "passive"))
    )
    (net (code "31") (name "/DRV11") (class "Default")
      (node (ref "Q11") (pin "1") (pinfunction "G_1") (pintype "passive"))
      (node (ref "R11") (pin "2") (pinfunction "2_2") (pintype "passive"))
    )
    (net (code "32") (name "/DRV12") (class "Default")
      (node (ref "Q12") (pin "1") (pinfunction "G_1") (pintype "passive"))
      (node (ref "R12") (pin "2") (pinfunction "2_2") (pintype "passive"))
    )
    (net (code "33") (name "/DRV13") (class "Default")
      (node (ref "Q13") (pin "1") (pinfunction "G_1") (pintype "passive"))
      (node (ref "R13") (pin "2") (pinfunction "2_2") (pintype "passive"))
    )
    (net (code "34") (name "/DRV14") (class "Default")
      (node (ref "Q14") (pin "1") (pinfunction "G_1") (pintype "passive"))
      (node (ref "R14") (pin "2") (pinfunction "2_2") (pintype "passive"))
    )
    (net (code "35") (name "/DRV15") (class "Default")
      (node (ref "Q15") (pin "1") (pinfunction "G_1") (pintype "passive"))
      (node (ref "R15") (pin "2") (pinfunction "2_2") (pintype "passive"))
    )
    (net (code "36") (name "/DRV16") (class "Default")
      (node (ref "Q16") (pin "1") (pinfunction "G_1") (pintype "passive"))
      (node (ref "R16") (pin "2") (pinfunction "2_2") (pintype "passive"))
    )
    (net (code "37") (name "/DRV17") (class "Default")
      (node (ref "Q17") (pin "1") (pinfunction "G_1") (pintype "passive"))
      (node (ref "R17") (pin "2") (pinfunction "2_2") (pintype "passive"))
    )
    (net (code "38") (name "/DRV18") (class "Default")
      (node (ref "Q18") (pin "1") (pinfunction "G_1") (pintype "passive"))
      (node (ref "R18") (pin "2") (pinfunction "2_2") (pintype "passive"))
    )
    (net (code "39") (name "/DRV19") (class "Default")
      (node (ref "Q19") (pin "1") (pinfunction "G_1") (pintype "passive"))
      (node (ref "R19") (pin "2") (pinfunction "2_2") (pintype "passive"))
    )
    (net (code "40") (name "/DRV20") (class "Default")
      (node (ref "Q20") (pin "1") (pinfunction "G_1") (pintype "passive"))
      (node (ref "R20") (pin "2") (pinfunction "2_2") (pintype "passive"))
    )
    (net (code "41") (name "/DRV21") (class "Default")
      (node (ref "Q21") (pin "1") (pinfunction "G_1") (pintype "passive"))
      (node (ref "R21") (pin "2") (pinfunction "2_2") (pintype "passive"))
    )
    (net (code "42") (name "/DRV22") (class "Default")
      (node (ref "Q22") (pin "1") (pinfunction "G_1") (pintype "passive"))
      (node (ref "R22") (pin "2") (pinfunction "2_2") (pintype "passive"))
    )
    (net (code "43") (name "/DRV23") (class "Default")
      (node (ref "Q23") (pin "1") (pinfunction "G_1") (pintype "passive"))
      (node (ref "R23") (pin "2") (pinfunction "2_2") (pintype "passive"))
    )
    (net (code "44") (name "/DRV24") (class "Default")
      (node (ref "Q24") (pin "1") (pinfunction "G_1") (pintype "passive"))
      (node (ref "R24") (pin "2") (pinfunction "2_2") (pintype "passive"))
    )
    (net (code "45") (name "/DRV25") (class "Default")
      (node (ref "Q25") (pin "1") (pinfunction "G_1") (pintype "passive"))
      (node (ref "R25") (pin "2") (pinfunction "2_2") (pintype "passive"))
    )
    (net (code "46") (name "/DRV26") (class "Default")
      (node (ref "Q26") (pin "1") (pinfunction "G_1") (pintype "passive"))
      (node (ref "R26") (pin "2") (pinfunction "2_2") (pintype "passive"))
    )
    (net (code "47") (name "/DRV27") (class "Default")
      (node (ref "Q27") (pin "1") (pinfunction "G_1") (pintype "passive"))
      (node (ref "R27") (pin "2") (pinfunction "2_2") (pintype "passive"))
    )
    (net (code "48") (name "/DRV28") (class "Default")
      (node (ref "Q28") (pin "1") (pinfunction "G_1") (pintype "passive"))
      (node (ref "R28") (pin "2") (pinfunction "2_2") (pintype "passive"))
    )
    (net (code "49") (name "/DRV29") (class "Default")
      (node (ref "Q29") (pin "1") (pinfunction "G_1") (pintype "passive"))
      (node (ref "R29") (pin "2") (pinfunction "2_2") (pintype "passive"))
    )
    (net (code "50") (name "/DRV30") (class "Default")
      (node (ref "Q30") (pin "1") (pinfunction "G_1") (pintype "passive"))
      (node (ref "R30") (pin "2") (pinfunction "2_2") (pintype "passive"))
    )
    (net (code "51") (name "/DRV31") (class "Default")
      (node (ref "Q31") (pin "1") (pinfunction "G_1") (pintype "passive"))
      (node (ref "R31") (pin "2") (pinfunction "2_2") (pintype "passive"))
    )
    (net (code "52") (name "/DRV32") (class "Default")
      (node (ref "Q32") (pin "1") (pinfunction "G_1") (pintype "passive"))
      (node (ref "R32") (pin "2") (pinfunction "2_2") (pintype "passive"))
    )
    (net (code "53") (name "/DRV33") (class "Default")
      (node (ref "Q33") (pin "1") (pinfunction "G_1") (pintype "passive"))
      (node (ref "R33") (pin "2") (pinfunction "2_2") (pintype "passive"))
    )
    (net (code "54") (name "/DRV34") (class "Default")
      (node (ref "Q34") (pin "1") (pinfunction "G_1") (pintype "passive"))
      (node (ref "R34") (pin "2") (pinfunction "2_2") (pintype "passive"))
    )
    (net (code "55") (name "/DRV35") (class "Default")
      (node (ref "Q35") (pin "1") (pinfunction "G_1") (pintype "passive"))
      (node (ref "R35") (pin "2") (pinfunction "2_2") (pintype "passive"))
    )
    (net (code "56") (name "/DRV36") (class "Default")
      (node (ref "Q36") (pin "1") (pinfunction "G_1") (pintype "passive"))
      (node (ref "R36") (pin "2") (pinfunction "2_2") (pintype "passive"))
    )
    (net (code "57") (name "/DRV37") (class "Default")
      (node (ref "Q37") (pin "1") (pinfunction "G_1") (pintype "passive"))
      (node (ref "R37") (pin "2") (pinfunction "2_2") (pintype "passive"))
    )
    (net (code "58") (name "/DRV38") (class "Default")
      (node (ref "Q38") (pin "1") (pinfunction "G_1") (pintype "passive"))
      (node (ref "R38") (pin "2") (pinfunction "2_2") (pintype "passive"))
    )
    (net (code "59") (name "/DRV39") (class "Default")
      (node (ref "Q39") (pin "1") (pinfunction "G_1") (pintype "passive"))
      (node (ref "R39") (pin "2") (pinfunction "2_2") (pintype "passive"))
    )
    (net (code "60") (name "/DRV40") (class "Default")
      (node (ref "Q40") (pin "1") (pinfunction "G_1") (pintype "passive"))
      (node (ref "R40") (pin "2") (pinfunction "2_2") (pintype "passive"))
    )
    (net (code "61") (name "/DRV41") (class "Default")
      (node (ref "Q41") (pin "1") (pinfunction "G_1") (pintype "passive"))
      (node (ref "R41") (pin "2") (pinfunction "2_2") (pintype "passive"))
    )
    (net (code "62") (name "/DRV42") (class "Default")
      (node (ref "Q42") (pin "1") (pinfunction "G_1") (pintype "passive"))
      (node (ref "R42") (pin "2") (pinfunction "2_2") (pintype "passive"))
    )
    (net (code "63") (name "/DRV43") (class "Default")
      (node (ref "Q43") (pin "1") (pinfunction "G_1") (pintype "passive"))
      (node (ref "R48") (pin "2") (pinfunction "2_2") (pintype "passive"))
    )
    (net (code "64") (name "/DRV44") (class "Default")
      (node (ref "Q44") (pin "1") (pinfunction "G_1") (pintype "passive"))
      (node (ref "R49") (pin "2") (pinfunction "2_2") (pintype "passive"))
    )
    (net (code "65") (name "/DRV45") (class "Default")
      (node (ref "Q45") (pin "1") (pinfunction "G_1") (pintype "passive"))
      (node (ref "R50") (pin "2") (pinfunction "2_2") (pintype "passive"))
    )
    (net (code "66") (name "/DRV46") (class "Default")
      (node (ref "Q46") (pin "1") (pinfunction "G_1") (pintype "passive"))
      (node (ref "R51") (pin "2") (pinfunction "2_2") (pintype "passive"))
    )
    (net (code "67") (name "/DRV47") (class "Default")
      (node (ref "Q47") (pin "1") (pinfunction "G_1") (pintype "passive"))
      (node (ref "R52") (pin "2") (pinfunction "2_2") (pintype "passive"))
    )
    (net (code "68") (name "/DRV48") (class "Default")
      (node (ref "Q48") (pin "1") (pinfunction "G_1") (pintype "passive"))
      (node (ref "R53") (pin "2") (pinfunction "2_2") (pintype "passive"))
    )
    (net (code "69") (name "/DRV49") (class "Default")
      (node (ref "Q49") (pin "1") (pinfunction "G_1") (pintype "passive"))
      (node (ref "R54") (pin "2") (pinfunction "2_2") (pintype "passive"))
    )
    (net (code "70") (name "/DRV50") (class "Default")
      (node (ref "Q50") (pin "1") (pinfunction "G_1") (pintype "passive"))
      (node (ref "R55") (pin "2") (pinfunction "2_2") (pintype "passive"))
    )
    (net (code "71") (name "/DRV51") (class "Default")
      (node (ref "Q51") (pin "1") (pinfunction "G_1") (pintype "passive"))
      (node (ref "R56") (pin "2") (pinfunction "2_2") (pintype "passive"))
    )
    (net (code "72") (name "/DRV52") (class "Default")
      (node (ref "Q52") (pin "1") (pinfunction "G_1") (pintype "passive"))
      (node (ref "R57") (pin "2") (pinfunction "2_2") (pintype "passive"))
    )
    (net (code "73") (name "/DRV53") (class "Default")
      (node (ref "Q53") (pin "1") (pinfunction "G_1") (pintype "passive"))
      (node (ref "R58") (pin "2") (pinfunction "2_2") (pintype "passive"))
    )
    (net (code "74") (name "/DRV54") (class "Default")
      (node (ref "Q54") (pin "1") (pinfunction "G_1") (pintype "passive"))
      (node (ref "R59") (pin "2") (pinfunction "2_2") (pintype "passive"))
    )
    (net (code "75") (name "/DRV55") (class "Default")
      (node (ref "Q55") (pin "1") (pinfunction "G_1") (pintype "passive"))
      (node (ref "R60") (pin "2") (pinfunction "2_2") (pintype "passive"))
    )
    (net (code "76") (name "/DRV56") (class "Default")
      (node (ref "Q56") (pin "1") (pinfunction "G_1") (pintype "passive"))
      (node (ref "R61") (pin "2") (pinfunction "2_2") (pintype "passive"))
    )
    (net (code "77") (name "/DRV57") (class "Default")
      (node (ref "Q57") (pin "1") (pinfunction "G_1") (pintype "passive"))
      (node (ref "R62") (pin "2") (pinfunction "2_2") (pintype "passive"))
    )
    (net (code "78") (name "/DRV58") (class "Default")
      (node (ref "Q58") (pin "1") (pinfunction "G_1") (pintype "passive"))
      (node (ref "R63") (pin "2") (pinfunction "2_2") (pintype "passive"))
    )
    (net (code "79") (name "/DRV59") (class "Default")
      (node (ref "Q59") (pin "1") (pinfunction "G_1") (pintype "passive"))
      (node (ref "R64") (pin "2") (pinfunction "2_2") (pintype "passive"))
    )
    (net (code "80") (name "/DRV60") (class "Default")
      (node (ref "Q60") (pin "1") (pinfunction "G_1") (pintype "passive"))
      (node (ref "R65") (pin "2") (pinfunction "2_2") (pintype "passive"))
    )
    (net (code "81") (name "/DRV61") (class "Default")
      (node (ref "Q61") (pin "1") (pinfunction "G_1") (pintype "passive"))
      (node (ref "R66") (pin "2") (pinfunction "2_2") (pintype "passive"))
    )
    (net (code "82") (name "/DRV62") (class "Default")
      (node (ref "Q62") (pin "1") (pinfunction "G_1") (pintype "passive"))
      (node (ref "R67") (pin "2") (pinfunction "2_2") (pintype "passive"))
    )
    (net (code "83") (name "/DRV63") (class "Default")
      (node (ref "Q63") (pin "1") (pinfunction "G_1") (pintype "passive"))
      (node (ref "R68") (pin "2") (pinfunction "2_2") (pintype "passive"))
    )
    (net (code "84") (name "/DRV64") (class "Default")
      (node (ref "Q64") (pin "1") (pinfunction "G_1") (pintype "passive"))
      (node (ref "R69") (pin "2") (pinfunction "2_2") (pintype "passive"))
    )
    (net (code "86") (name "/FUN") (class "Default")
      (node (ref "X4") (pin "A10") (pinfunction "A10_A10") (pintype "passive"))
    )
    (net (code "87") (name "/MISO") (class "Default")
      (node (ref "X4") (pin "A15") (pinfunction "A15_A15") (pintype "passive"))
    )
    (net (code "88") (name "/MOSI") (class "Default")
      (node (ref "X4") (pin "A14") (pinfunction "A14_A14") (pintype "passive"))
    )
    (net (code "89") (name "/RST") (class "Default")
      (node (ref "Q69") (pin "1") (pinfunction "G_1") (pintype "passive"))
      (node (ref "R130") (pin "2") (pinfunction "2_2") (pintype "passive"))
      (node (ref "X4") (pin "B10") (pinfunction "B10_B10") (pintype "passive"))
    )
    (net (code "90") (name "/SCLK") (class "Default")
      (node (ref "X4") (pin "B14") (pinfunction "B14_B14") (pintype "passive"))
    )
    (net (code "91") (name "/nPOR") (class "Default")
      (node (ref "Q69") (pin "3") (pinfunction "D_3") (pintype "passive"))
    )
    (net (code "99") (name "3V3IO") (class "Default")
      (node (ref "J12") (pin "1") (pinfunction "1_1") (pintype "passive"))
      (node (ref "R121") (pin "2") (pinfunction "2_2") (pintype "passive"))
    )
    (net (code "100") (name "5V0R") (class "Default")
      (node (ref "D12") (pin "1") (pinfunction "Anode_1") (pintype "passive"))
      (node (ref "K1") (pin "1") (pinfunction "+_1") (pintype "passive"))
      (node (ref "K10") (pin "1") (pinfunction "+_1") (pintype "passive"))
      (node (ref "K11") (pin "1") (pinfunction "+_1") (pintype "passive"))
      (node (ref "K12") (pin "1") (pinfunction "+_1") (pintype "passive"))
      (node (ref "K13") (pin "1") (pinfunction "+_1") (pintype "passive"))
      (node (ref "K14") (pin "1") (pinfunction "+_1") (pintype "passive"))
      (node (ref "K15") (pin "1") (pinfunction "+_1") (pintype "passive"))
      (node (ref "K16") (pin "1") (pinfunction "+_1") (pintype "passive"))
      (node (ref "K17") (pin "1") (pinfunction "+_1") (pintype "passive"))
      (node (ref "K18") (pin "1") (pinfunction "+_1") (pintype "passive"))
      (node (ref "K19") (pin "1") (pinfunction "+_1") (pintype "passive"))
      (node (ref "K2") (pin "1") (pinfunction "+_1") (pintype "passive"))
      (node (ref "K20") (pin "1") (pinfunction "+_1") (pintype "passive"))
      (node (ref "K21") (pin "1") (pinfunction "+_1") (pintype "passive"))
      (node (ref "K22") (pin "1") (pinfunction "+_1") (pintype "passive"))
      (node (ref "K23") (pin "1") (pinfunction "+_1") (pintype "passive"))
      (node (ref "K24") (pin "1") (pinfunction "+_1") (pintype "passive"))
      (node (ref "K25") (pin "1") (pinfunction "+_1") (pintype "passive"))
      (node (ref "K26") (pin "1") (pinfunction "+_1") (pintype "passive"))
      (node (ref "K27") (pin "1") (pinfunction "+_1") (pintype "passive"))
      (node (ref "K28") (pin "1") (pinfunction "+_1") (pintype "passive"))
      (node (ref "K29") (pin "1") (pinfunction "+_1") (pintype "passive"))
      (node (ref "K3") (pin "1") (pinfunction "+_1") (pintype "passive"))
      (node (ref "K30") (pin "1") (pinfunction "+_1") (pintype "passive"))
      (node (ref "K31") (pin "1") (pinfunction "+_1") (pintype "passive"))
      (node (ref "K32") (pin "1") (pinfunction "+_1") (pintype "passive"))
      (node (ref "K33") (pin "1") (pinfunction "+_1") (pintype "passive"))
      (node (ref "K34") (pin "1") (pinfunction "+_1") (pintype "passive"))
      (node (ref "K35") (pin "1") (pinfunction "+_1") (pintype "passive"))
      (node (ref "K36") (pin "1") (pinfunction "+_1") (pintype "passive"))
      (node (ref "K37") (pin "1") (pinfunction "+_1") (pintype "passive"))
      (node (ref "K38") (pin "1") (pinfunction "+_1") (pintype "passive"))
      (node (ref "K39") (pin "1") (pinfunction "+_1") (pintype "passive"))
      (node (ref "K4") (pin "1") (pinfunction "+_1") (pintype "passive"))
      (node (ref "K40") (pin "1") (pinfunction "+_1") (pintype "passive"))
      (node (ref "K41") (pin "1") (pinfunction "+_1") (pintype "passive"))
      (node (ref "K42") (pin "1") (pinfunction "+_1") (pintype "passive"))
      (node (ref "K43") (pin "1") (pinfunction "+_1") (pintype "passive"))
      (node (ref "K44") (pin "1") (pinfunction "+_1") (pintype "passive"))
      (node (ref "K45") (pin "1") (pinfunction "+_1") (pintype "passive"))
      (node (ref "K46") (pin "1") (pinfunction "+_1") (pintype "passive"))
      (node (ref "K47") (pin "1") (pinfunction "+_1") (pintype "passive"))
      (node (ref "K48") (pin "1") (pinfunction "+_1") (pintype "passive"))
      (node (ref "K49") (pin "1") (pinfunction "+_1") (pintype "passive"))
      (node (ref "K5") (pin "1") (pinfunction "+_1") (pintype "passive"))
      (node (ref "K50") (pin "1") (pinfunction "+_1") (pintype "passive"))
      (node (ref "K51") (pin "1") (pinfunction "+_1") (pintype "passive"))
      (node (ref "K52") (pin "1") (pinfunction "+_1") (pintype "passive"))
      (node (ref "K53") (pin "1") (pinfunction "+_1") (pintype "passive"))
      (node (ref "K54") (pin "1") (pinfunction "+_1") (pintype "passive"))
      (node (ref "K55") (pin "1") (pinfunction "+_1") (pintype "passive"))
      (node (ref "K56") (pin "1") (pinfunction "+_1") (pintype "passive"))
      (node (ref "K57") (pin "1") (pinfunction "+_1") (pintype "passive"))
      (node (ref "K58") (pin "1") (pinfunction "+_1") (pintype "passive"))
      (node (ref "K59") (pin "1") (pinfunction "+_1") (pintype "passive"))
      (node (ref "K6") (pin "1") (pinfunction "+_1") (pintype "passive"))
      (node (ref "K60") (pin "1") (pinfunction "+_1") (pintype "passive"))
      (node (ref "K61") (pin "1") (pinfunction "+_1") (pintype "passive"))
      (node (ref "K62") (pin "1") (pinfunction "+_1") (pintype "passive"))
      (node (ref "K63") (pin "1") (pinfunction "+_1") (pintype "passive"))
      (node (ref "K64") (pin "1") (pinfunction "+_1") (pintype "passive"))
      (node (ref "K7") (pin "1") (pinfunction "+_1") (pintype "passive"))
      (node (ref "K8") (pin "1") (pinfunction "+_1") (pintype "passive"))
      (node (ref "K9") (pin "1") (pinfunction "+_1") (pintype "passive"))
      (node (ref "TP5") (pin "1") (pinfunction "1_1") (pintype "passive"))
      (node (ref "X4") (pin "A7") (pinfunction "A7_A7") (pintype "passive"))
      (node (ref "X4") (pin "A8") (pinfunction "A8_A8") (pintype "passive"))
      (node (ref "X4") (pin "A9") (pinfunction "A9_A9") (pintype "passive"))
      (node (ref "X4") (pin "B7") (pinfunction "B7_B7") (pintype "passive"))
      (node (ref "X4") (pin "B8") (pinfunction "B8_B8") (pintype "passive"))
      (node (ref "X4") (pin "B9") (pinfunction "B9_B9") (pintype "passive"))
    )
    (net (code "101") (name "12V0") (class "Default")
      (node (ref "J11") (pin "1") (pinfunction "1_1") (pintype "passive"))
      (node (ref "TP6") (pin "1") (pinfunction "1_1") (pintype "passive"))
      (node (ref "X4") (pin "A11") (pinfunction "A11_A11") (pintype "passive"))
      (node (ref "X4") (pin "A12") (pinfunction "A12_A12") (pintype "passive"))
      (node (ref "X4") (pin "B11") (pinfunction "B11_B11") (pintype "passive"))
      (node (ref "X4") (pin "B12") (pinfunction "B12_B12") (pintype "passive"))
    )
    (net (code "102") (name "GND") (class "Default")
      (node (ref "J11") (pin "10") (pinfunction "10_10") (pintype "passive"))
      (node (ref "J11") (pin "2") (pinfunction "2_2") (pintype "passive"))
      (node (ref "J11") (pin "4") (pinfunction "4_4") (pintype "passive"))
      (node (ref "J11") (pin "6") (pinfunction "6_6") (pintype "passive"))
      (node (ref "J11") (pin "8") (pinfunction "8_8") (pintype "passive"))
      (node (ref "Q1") (pin "2") (pinfunction "S_2") (pintype "passive"))
      (node (ref "Q10") (pin "2") (pinfunction "S_2") (pintype "passive"))
      (node (ref "Q11") (pin "2") (pinfunction "S_2") (pintype "passive"))
      (node (ref "Q12") (pin "2") (pinfunction "S_2") (pintype "passive"))
      (node (ref "Q13") (pin "2") (pinfunction "S_2") (pintype "passive"))
      (node (ref "Q14") (pin "2") (pinfunction "S_2") (pintype "passive"))
      (node (ref "Q15") (pin "2") (pinfunction "S_2") (pintype "passive"))
      (node (ref "Q16") (pin "2") (pinfunction "S_2") (pintype "passive"))
      (node (ref "Q17") (pin "2") (pinfunction "S_2") (pintype "passive"))
      (node (ref "Q18") (pin "2") (pinfunction "S_2") (pintype "passive"))
      (node (ref "Q19") (pin "2") (pinfunction "S_2") (pintype "passive"))
      (node (ref "Q2") (pin "2") (pinfunction "S_2") (pintype "passive"))
      (node (ref "Q20") (pin "2") (pinfunction "S_2") (pintype "passive"))
      (node (ref "Q21") (pin "2") (pinfunction "S_2") (pintype "passive"))
      (node (ref "Q22") (pin "2") (pinfunction "S_2") (pintype "passive"))
      (node (ref "Q23") (pin "2") (pinfunction "S_2") (pintype "passive"))
      (node (ref "Q24") (pin "2") (pinfunction "S_2") (pintype "passive"))
      (node (ref "Q25") (pin "2") (pinfunction "S_2") (pintype "passive"))
      (node (ref "Q26") (pin "2") (pinfunction "S_2") (pintype "passive"))
      (node (ref "Q27") (pin "2") (pinfunction "S_2") (pintype "passive"))
      (node (ref "Q28") (pin "2") (pinfunction "S_2") (pintype "passive"))
      (node (ref "Q29") (pin "2") (pinfunction "S_2") (pintype "passive"))
      (node (ref "Q3") (pin "2") (pinfunction "S_2") (pintype "passive"))
      (node (ref "Q30") (pin "2") (pinfunction "S_2") (pintype "passive"))
      (node (ref "Q31") (pin "2") (pinfunction "S_2") (pintype "passive"))
      (node (ref "Q32") (pin "2") (pinfunction "S_2") (pintype "passive"))
      (node (ref "Q33") (pin "2") (pinfunction "S_2") (pintype "passive"))
      (node (ref "Q34") (pin "2") (pinfunction "S_2") (pintype "passive"))
      (node (ref "Q35") (pin "2") (pinfunction "S_2") (pintype "passive"))
      (node (ref "Q36") (pin "2") (pinfunction "S_2") (pintype "passive"))
      (node (ref "Q37") (pin "2") (pinfunction "S_2") (pintype "passive"))
      (node (ref "Q38") (pin "2") (pinfunction "S_2") (pintype "passive"))
      (node (ref "Q39") (pin "2") (pinfunction "S_2") (pintype "passive"))
      (node (ref "Q4") (pin "2") (pinfunction "S_2") (pintype "passive"))
      (node (ref "Q40") (pin "2") (pinfunction "S_2") (pintype "passive"))
      (node (ref "Q41") (pin "2") (pinfunction "S_2") (pintype "passive"))
      (node (ref "Q42") (pin "2") (pinfunction "S_2") (pintype "passive"))
      (node (ref "Q43") (pin "2") (pinfunction "S_2") (pintype "passive"))
      (node (ref "Q44") (pin "2") (pinfunction "S_2") (pintype "passive"))
      (node (ref "Q45") (pin "2") (pinfunction "S_2") (pintype "passive"))
      (node (ref "Q46") (pin "2") (pinfunction "S_2") (pintype "passive"))
      (node (ref "Q47") (pin "2") (pinfunction "S_2") (pintype "passive"))
      (node (ref "Q48") (pin "2") (pinfunction "S_2") (pintype "passive"))
      (node (ref "Q49") (pin "2") (pinfunction "S_2") (pintype "passive"))
      (node (ref "Q5") (pin "2") (pinfunction "S_2") (pintype "passive"))
      (node (ref "Q50") (pin "2") (pinfunction "S_2") (pintype "passive"))
      (node (ref "Q51") (pin "2") (pinfunction "S_2") (pintype "passive"))
      (node (ref "Q52") (pin "2") (pinfunction "S_2") (pintype "passive"))
      (node (ref "Q53") (pin "2") (pinfunction "S_2") (pintype "passive"))
      (node (ref "Q54") (pin "2") (pinfunction "S_2") (pintype "passive"))
      (node (ref "Q55") (pin "2") (pinfunction "S_2") (pintype "passive"))
      (node (ref "Q56") (pin "2") (pinfunction "S_2") (pintype "passive"))
      (node (ref "Q57") (pin "2") (pinfunction "S_2") (pintype "passive"))
      (node (ref "Q58") (pin "2") (pinfunction "S_2") (pintype "passive"))
      (node (ref "Q59") (pin "2") (pinfunction "S_2") (pintype "passive"))
      (node (ref "Q6") (pin "2") (pinfunction "S_2") (pintype "passive"))
      (node (ref "Q60") (pin "2") (pinfunction "S_2") (pintype "passive"))
      (node (ref "Q61") (pin "2") (pinfunction "S_2") (pintype "passive"))
      (node (ref "Q62") (pin "2") (pinfunction "S_2") (pintype "passive"))
      (node (ref "Q63") (pin "2") (pinfunction "S_2") (pintype "passive"))
      (node (ref "Q64") (pin "2") (pinfunction "S_2") (pintype "passive"))
      (node (ref "Q69") (pin "2") (pinfunction "S_2") (pintype "passive"))
      (node (ref "Q7") (pin "2") (pinfunction "S_2") (pintype "passive"))
      (node (ref "Q8") (pin "2") (pinfunction "S_2") (pintype "passive"))
      (node (ref "Q9") (pin "2") (pinfunction "S_2") (pintype "passive"))
      (node (ref "R1") (pin "1") (pinfunction "1_1") (pintype "passive"))
      (node (ref "R10") (pin "1") (pinfunction "1_1") (pintype "passive"))
      (node (ref "R11") (pin "1") (pinfunction "1_1") (pintype "passive"))
      (node (ref "R12") (pin "1") (pinfunction "1_1") (pintype "passive"))
      (node (ref "R125") (pin "1") (pinfunction "1_1") (pintype "passive"))
      (node (ref "R13") (pin "1") (pinfunction "1_1") (pintype "passive"))
      (node (ref "R130") (pin "1") (pinfunction "1_1") (pintype "passive"))
      (node (ref "R14") (pin "1") (pinfunction "1_1") (pintype "passive"))
      (node (ref "R15") (pin "1") (pinfunction "1_1") (pintype "passive"))
      (node (ref "R16") (pin "1") (pinfunction "1_1") (pintype "passive"))
      (node (ref "R17") (pin "1") (pinfunction "1_1") (pintype "passive"))
      (node (ref "R18") (pin "1") (pinfunction "1_1") (pintype "passive"))
      (node (ref "R19") (pin "1") (pinfunction "1_1") (pintype "passive"))
      (node (ref "R2") (pin "1") (pinfunction "1_1") (pintype "passive"))
      (node (ref "R20") (pin "1") (pinfunction "1_1") (pintype "passive"))
      (node (ref "R21") (pin "1") (pinfunction "1_1") (pintype "passive"))
      (node (ref "R22") (pin "1") (pinfunction "1_1") (pintype "passive"))
      (node (ref "R23") (pin "1") (pinfunction "1_1") (pintype "passive"))
      (node (ref "R24") (pin "1") (pinfunction "1_1") (pintype "passive"))
      (node (ref "R25") (pin "1") (pinfunction "1_1") (pintype "passive"))
      (node (ref "R26") (pin "1") (pinfunction "1_1") (pintype "passive"))
      (node (ref "R27") (pin "1") (pinfunction "1_1") (pintype "passive"))
      (node (ref "R28") (pin "1") (pinfunction "1_1") (pintype "passive"))
      (node (ref "R29") (pin "1") (pinfunction "1_1") (pintype "passive"))
      (node (ref "R3") (pin "1") (pinfunction "1_1") (pintype "passive"))
      (node (ref "R30") (pin "1") (pinfunction "1_1") (pintype "passive"))
      (node (ref "R31") (pin "1") (pinfunction "1_1") (pintype "passive"))
      (node (ref "R32") (pin "1") (pinfunction "1_1") (pintype "passive"))
      (node (ref "R33") (pin "1") (pinfunction "1_1") (pintype "passive"))
      (node (ref "R34") (pin "1") (pinfunction "1_1") (pintype "passive"))
      (node (ref "R35") (pin "1") (pinfunction "1_1") (pintype "passive"))
      (node (ref "R36") (pin "1") (pinfunction "1_1") (pintype "passive"))
      (node (ref "R37") (pin "1") (pinfunction "1_1") (pintype "passive"))
      (node (ref "R38") (pin "1") (pinfunction "1_1") (pintype "passive"))
      (node (ref "R39") (pin "1") (pinfunction "1_1") (pintype "passive"))
      (node (ref "R4") (pin "1") (pinfunction "1_1") (pintype "passive"))
      (node (ref "R40") (pin "1") (pinfunction "1_1") (pintype "passive"))
      (node (ref "R41") (pin "1") (pinfunction "1_1") (pintype "passive"))
      (node (ref "R42") (pin "1") (pinfunction "1_1") (pintype "passive"))
      (node (ref "R48") (pin "1") (pinfunction "1_1") (pintype "passive"))
      (node (ref "R49") (pin "1") (pinfunction "1_1") (pintype "passive"))
      (node (ref "R5") (pin "1") (pinfunction "1_1") (pintype "passive"))
      (node (ref "R50") (pin "1") (pinfunction "1_1") (pintype "passive"))
      (node (ref "R51") (pin "1") (pinfunction "1_1") (pintype "passive"))
      (node (ref "R52") (pin "1") (pinfunction "1_1") (pintype "passive"))
      (node (ref "R53") (pin "1") (pinfunction "1_1") (pintype "passive"))
      (node (ref "R54") (pin "1") (pinfunction "1_1") (pintype "passive"))
      (node (ref "R55") (pin "1") (pinfunction "1_1") (pintype "passive"))
      (node (ref "R56") (pin "1") (pinfunction "1_1") (pintype "passive"))
      (node (ref "R57") (pin "1") (pinfunction "1_1") (pintype "passive"))
      (node (ref "R58") (pin "1") (pinfunction "1_1") (pintype "passive"))
      (node (ref "R59") (pin "1") (pinfunction "1_1") (pintype "passive"))
      (node (ref "R6") (pin "1") (pinfunction "1_1") (pintype "passive"))
      (node (ref "R60") (pin "1") (pinfunction "1_1") (pintype "passive"))
      (node (ref "R61") (pin "1") (pinfunction "1_1") (pintype "passive"))
      (node (ref "R62") (pin "1") (pinfunction "1_1") (pintype "passive"))
      (node (ref "R63") (pin "1") (pinfunction "1_1") (pintype "passive"))
      (node (ref "R64") (pin "1") (pinfunction "1_1") (pintype "passive"))
      (node (ref "R65") (pin "1") (pinfunction "1_1") (pintype "passive"))
      (node (ref "R66") (pin "1") (pinfunction "1_1") (pintype "passive"))
      (node (ref "R67") (pin "1") (pinfunction "1_1") (pintype "passive"))
      (node (ref "R68") (pin "1") (pinfunction "1_1") (pintype "passive"))
      (node (ref "R69") (pin "1") (pinfunction "1_1") (pintype "passive"))
      (node (ref "R7") (pin "1") (pinfunction "1_1") (pintype "passive"))
      (node (ref "R8") (pin "1") (pinfunction "1_1") (pintype "passive"))
      (node (ref "R9") (pin "1") (pinfunction "1_1") (pintype "passive"))
      (node (ref "TP5") (pin "2") (pinfunction "2_2") (pintype "passive"))
      (node (ref "TP6") (pin "2") (pinfunction "2_2") (pintype "passive"))
      (node (ref "X4") (pin "A1") (pinfunction "A1_A1") (pintype "passive"))
      (node (ref "X4") (pin "A13") (pinfunction "A13_A13") (pintype "passive"))
      (node (ref "X4") (pin "A16") (pinfunction "A16_A16") (pintype "passive"))
      (node (ref "X4") (pin "A6") (pinfunction "A6_A6") (pintype "passive"))
      (node (ref "X4") (pin "B1") (pinfunction "B1_B1") (pintype "passive"))
      (node (ref "X4") (pin "B13") (pinfunction "B13_B13") (pintype "passive"))
      (node (ref "X4") (pin "B16") (pinfunction "B16_B16") (pintype "passive"))
      (node (ref "X4") (pin "B6") (pinfunction "B6_B6") (pintype "passive"))
    )
    (net (code "103") (name "Net-(D12-Cathode)") (class "Default")
      (node (ref "D12") (pin "2") (pinfunction "Cathode_2") (pintype "passive"))
      (node (ref "R125") (pin "2") (pinfunction "2_2") (pintype "passive"))
    )
    (net (code "104") (name "Net-(J11-Pad3)") (class "Default")
      (node (ref "J11") (pin "3") (pinfunction "3_3") (pintype "passive"))
      (node (ref "J12") (pin "2") (pinfunction "2_2") (pintype "passive"))
    )
    (net (code "105") (name "Net-(K1A-CA)") (class "Default")
      (node (ref "K1") (pin "3") (pinfunction "CA_3") (pintype "passive"))
      (node (ref "X3") (pin "1") (pinfunction "1_1") (pintype "passive"))
    )
    (net (code "106") (name "Net-(K1A-CB)") (class "Default")
      (node (ref "K1") (pin "4") (pinfunction "CB_4") (pintype "passive"))
      (node (ref "X2") (pin "1") (pinfunction "1_1") (pintype "passive"))
    )
    (net (code "107") (name "Net-(K1B--)") (class "Default")
      (node (ref "K1") (pin "2") (pinfunction "-_2") (pintype "passive"))
      (node (ref "Q1") (pin "3") (pinfunction "D_3") (pintype "passive"))
    )
    (net (code "108") (name "Net-(K2A-CA)") (class "Default")
      (node (ref "K2") (pin "3") (pinfunction "CA_3") (pintype "passive"))
      (node (ref "X3") (pin "2") (pinfunction "2_2") (pintype "passive"))
    )
    (net (code "109") (name "Net-(K2A-CB)") (class "Default")
      (node (ref "K2") (pin "4") (pinfunction "CB_4") (pintype "passive"))
      (node (ref "X2") (pin "2") (pinfunction "2_2") (pintype "passive"))
    )
    (net (code "110") (name "Net-(K2B--)") (class "Default")
      (node (ref "K2") (pin "2") (pinfunction "-_2") (pintype "passive"))
      (node (ref "Q2") (pin "3") (pinfunction "D_3") (pintype "passive"))
    )
    (net (code "111") (name "Net-(K3A-CA)") (class "Default")
      (node (ref "K3") (pin "3") (pinfunction "CA_3") (pintype "passive"))
      (node (ref "X3") (pin "3") (pinfunction "3_3") (pintype "passive"))
    )
    (net (code "112") (name "Net-(K3A-CB)") (class "Default")
      (node (ref "K3") (pin "4") (pinfunction "CB_4") (pintype "passive"))
      (node (ref "X2") (pin "3") (pinfunction "3_3") (pintype "passive"))
    )
    (net (code "113") (name "Net-(K3B--)") (class "Default")
      (node (ref "K3") (pin "2") (pinfunction "-_2") (pintype "passive"))
      (node (ref "Q3") (pin "3") (pinfunction "D_3") (pintype "passive"))
    )
    (net (code "114") (name "Net-(K4A-CA)") (class "Default")
      (node (ref "K4") (pin "3") (pinfunction "CA_3") (pintype "passive"))
      (node (ref "X3") (pin "4") (pinfunction "4_4") (pintype "passive"))
    )
    (net (code "115") (name "Net-(K4A-CB)") (class "Default")
      (node (ref "K4") (pin "4") (pinfunction "CB_4") (pintype "passive"))
      (node (ref "X2") (pin "4") (pinfunction "4_4") (pintype "passive"))
    )
    (net (code "116") (name "Net-(K4B--)") (class "Default")
      (node (ref "K4") (pin "2") (pinfunction "-_2") (pintype "passive"))
      (node (ref "Q4") (pin "3") (pinfunction "D_3") (pintype "passive"))
    )
    (net (code "117") (name "Net-(K5A-CA)") (class "Default")
      (node (ref "K5") (pin "3") (pinfunction "CA_3") (pintype "passive"))
      (node (ref "X3") (pin "5") (pinfunction "5_5") (pintype "passive"))
    )
    (net (code "118") (name "Net-(K5A-CB)") (class "Default")
      (node (ref "K5") (pin "4") (pinfunction "CB_4") (pintype "passive"))
      (node (ref "X2") (pin "5") (pinfunction "5_5") (pintype "passive"))
    )
    (net (code "119") (name "Net-(K5B--)") (class "Default")
      (node (ref "K5") (pin "2") (pinfunction "-_2") (pintype "passive"))
      (node (ref "Q5") (pin "3") (pinfunction "D_3") (pintype "passive"))
    )
    (net (code "120") (name "Net-(K6A-CA)") (class "Default")
      (node (ref "K6") (pin "3") (pinfunction "CA_3") (pintype "passive"))
      (node (ref "X3") (pin "6") (pinfunction "6_6") (pintype "passive"))
    )
    (net (code "121") (name "Net-(K6A-CB)") (class "Default")
      (node (ref "K6") (pin "4") (pinfunction "CB_4") (pintype "passive"))
      (node (ref "X2") (pin "6") (pinfunction "6_6") (pintype "passive"))
    )
    (net (code "122") (name "Net-(K6B--)") (class "Default")
      (node (ref "K6") (pin "2") (pinfunction "-_2") (pintype "passive"))
      (node (ref "Q6") (pin "3") (pinfunction "D_3") (pintype "passive"))
    )
    (net (code "123") (name "Net-(K7A-CA)") (class "Default")
      (node (ref "K7") (pin "3") (pinfunction "CA_3") (pintype "passive"))
      (node (ref "X3") (pin "7") (pinfunction "7_7") (pintype "passive"))
    )
    (net (code "124") (name "Net-(K7A-CB)") (class "Default")
      (node (ref "K7") (pin "4") (pinfunction "CB_4") (pintype "passive"))
      (node (ref "X2") (pin "7") (pinfunction "7_7") (pintype "passive"))
    )
    (net (code "125") (name "Net-(K7B--)") (class "Default")
      (node (ref "K7") (pin "2") (pinfunction "-_2") (pintype "passive"))
      (node (ref "Q7") (pin "3") (pinfunction "D_3") (pintype "passive"))
    )
    (net (code "126") (name "Net-(K8A-CA)") (class "Default")
      (node (ref "K8") (pin "3") (pinfunction "CA_3") (pintype "passive"))
      (node (ref "X3") (pin "8") (pinfunction "8_8") (pintype "passive"))
    )
    (net (code "127") (name "Net-(K8A-CB)") (class "Default")
      (node (ref "K8") (pin "4") (pinfunction "CB_4") (pintype "passive"))
      (node (ref "X2") (pin "8") (pinfunction "8_8") (pintype "passive"))
    )
    (net (code "128") (name "Net-(K8B--)") (class "Default")
      (node (ref "K8") (pin "2") (pinfunction "-_2") (pintype "passive"))
      (node (ref "Q8") (pin "3") (pinfunction "D_3") (pintype "passive"))
    )
    (net (code "129") (name "Net-(K9A-CA)") (class "Default")
      (node (ref "K9") (pin "3") (pinfunction "CA_3") (pintype "passive"))
      (node (ref "X3") (pin "9") (pinfunction "9_9") (pintype "passive"))
    )
    (net (code "130") (name "Net-(K9A-CB)") (class "Default")
      (node (ref "K9") (pin "4") (pinfunction "CB_4") (pintype "passive"))
      (node (ref "X2") (pin "9") (pinfunction "9_9") (pintype "passive"))
    )
    (net (code "131") (name "Net-(K9B--)") (class "Default")
      (node (ref "K9") (pin "2") (pinfunction "-_2") (pintype "passive"))
      (node (ref "Q9") (pin "3") (pinfunction "D_3") (pintype "passive"))
    )
    (net (code "132") (name "Net-(K10A-CA)") (class "Default")
      (node (ref "K10") (pin "3") (pinfunction "CA_3") (pintype "passive"))
      (node (ref "X3") (pin "10") (pinfunction "10_10") (pintype "passive"))
    )
    (net (code "133") (name "Net-(K10A-CB)") (class "Default")
      (node (ref "K10") (pin "4") (pinfunction "CB_4") (pintype "passive"))
      (node (ref "X2") (pin "10") (pinfunction "10_10") (pintype "passive"))
    )
    (net (code "134") (name "Net-(K10B--)") (class "Default")
      (node (ref "K10") (pin "2") (pinfunction "-_2") (pintype "passive"))
      (node (ref "Q10") (pin "3") (pinfunction "D_3") (pintype "passive"))
    )
    (net (code "135") (name "Net-(K11A-CA)") (class "Default")
      (node (ref "K11") (pin "3") (pinfunction "CA_3") (pintype "passive"))
      (node (ref "X3") (pin "11") (pinfunction "11_11") (pintype "passive"))
    )
    (net (code "136") (name "Net-(K11A-CB)") (class "Default")
      (node (ref "K11") (pin "4") (pinfunction "CB_4") (pintype "passive"))
      (node (ref "X2") (pin "11") (pinfunction "11_11") (pintype "passive"))
    )
    (net (code "137") (name "Net-(K11B--)") (class "Default")
      (node (ref "K11") (pin "2") (pinfunction "-_2") (pintype "passive"))
      (node (ref "Q11") (pin "3") (pinfunction "D_3") (pintype "passive"))
    )
    (net (code "138") (name "Net-(K12A-CA)") (class "Default")
      (node (ref "K12") (pin "3") (pinfunction "CA_3") (pintype "passive"))
      (node (ref "X3") (pin "12") (pinfunction "12_12") (pintype "passive"))
    )
    (net (code "139") (name "Net-(K12A-CB)") (class "Default")
      (node (ref "K12") (pin "4") (pinfunction "CB_4") (pintype "passive"))
      (node (ref "X2") (pin "12") (pinfunction "12_12") (pintype "passive"))
    )
    (net (code "140") (name "Net-(K12B--)") (class "Default")
      (node (ref "K12") (pin "2") (pinfunction "-_2") (pintype "passive"))
      (node (ref "Q12") (pin "3") (pinfunction "D_3") (pintype "passive"))
    )
    (net (code "141") (name "Net-(K13A-CA)") (class "Default")
      (node (ref "K13") (pin "3") (pinfunction "CA_3") (pintype "passive"))
      (node (ref "X3") (pin "13") (pinfunction "13_13") (pintype "passive"))
    )
    (net (code "142") (name "Net-(K13A-CB)") (class "Default")
      (node (ref "K13") (pin "4") (pinfunction "CB_4") (pintype "passive"))
      (node (ref "X2") (pin "13") (pinfunction "13_13") (pintype "passive"))
    )
    (net (code "143") (name "Net-(K13B--)") (class "Default")
      (node (ref "K13") (pin "2") (pinfunction "-_2") (pintype "passive"))
      (node (ref "Q13") (pin "3") (pinfunction "D_3") (pintype "passive"))
    )
    (net (code "144") (name "Net-(K14A-CA)") (class "Default")
      (node (ref "K14") (pin "3") (pinfunction "CA_3") (pintype "passive"))
      (node (ref "X3") (pin "14") (pinfunction "14_14") (pintype "passive"))
    )
    (net (code "145") (name "Net-(K14A-CB)") (class "Default")
      (node (ref "K14") (pin "4") (pinfunction "CB_4") (pintype "passive"))
      (node (ref "X2") (pin "14") (pinfunction "14_14") (pintype "passive"))
    )
    (net (code "146") (name "Net-(K14B--)") (class "Default")
      (node (ref "K14") (pin "2") (pinfunction "-_2") (pintype "passive"))
      (node (ref "Q14") (pin "3") (pinfunction "D_3") (pintype "passive"))
    )
    (net (code "147") (name "Net-(K15A-CA)") (class "Default")
      (node (ref "K15") (pin "3") (pinfunction "CA_3") (pintype "passive"))
      (node (ref "X3") (pin "15") (pinfunction "15_15") (pintype "passive"))
    )
    (net (code "148") (name "Net-(K15A-CB)") (class "Default")
      (node (ref "K15") (pin "4") (pinfunction "CB_4") (pintype "passive"))
      (node (ref "X2") (pin "15") (pinfunction "15_15") (pintype "passive"))
    )
    (net (code "149") (name "Net-(K15B--)") (class "Default")
      (node (ref "K15") (pin "2") (pinfunction "-_2") (pintype "passive"))
      (node (ref "Q15") (pin "3") (pinfunction "D_3") (pintype "passive"))
    )
    (net (code "150") (name "Net-(K16A-CA)") (class "Default")
      (node (ref "K16") (pin "3") (pinfunction "CA_3") (pintype "passive"))
      (node (ref "X3") (pin "16") (pinfunction "16_16") (pintype "passive"))
    )
    (net (code "151") (name "Net-(K16A-CB)") (class "Default")
      (node (ref "K16") (pin "4") (pinfunction "CB_4") (pintype "passive"))
      (node (ref "X2") (pin "16") (pinfunction "16_16") (pintype "passive"))
    )
    (net (code "152") (name "Net-(K16B--)") (class "Default")
      (node (ref "K16") (pin "2") (pinfunction "-_2") (pintype "passive"))
      (node (ref "Q16") (pin "3") (pinfunction "D_3") (pintype "passive"))
    )
    (net (code "153") (name "Net-(K17A-CA)") (class "Default")
      (node (ref "K17") (pin "3") (pinfunction "CA_3") (pintype "passive"))
      (node (ref "X3") (pin "17") (pinfunction "17_17") (pintype "passive"))
    )
    (net (code "154") (name "Net-(K17A-CB)") (class "Default")
      (node (ref "K17") (pin "4") (pinfunction "CB_4") (pintype "passive"))
      (node (ref "X2") (pin "17") (pinfunction "17_17") (pintype "passive"))
    )
    (net (code "155") (name "Net-(K17B--)") (class "Default")
      (node (ref "K17") (pin "2") (pinfunction "-_2") (pintype "passive"))
      (node (ref "Q17") (pin "3") (pinfunction "D_3") (pintype "passive"))
    )
    (net (code "156") (name "Net-(K18A-CA)") (class "Default")
      (node (ref "K18") (pin "3") (pinfunction "CA_3") (pintype "passive"))
      (node (ref "X3") (pin "18") (pinfunction "18_18") (pintype "passive"))
    )
    (net (code "157") (name "Net-(K18A-CB)") (class "Default")
      (node (ref "K18") (pin "4") (pinfunction "CB_4") (pintype "passive"))
      (node (ref "X2") (pin "18") (pinfunction "18_18") (pintype "passive"))
    )
    (net (code "158") (name "Net-(K18B--)") (class "Default")
      (node (ref "K18") (pin "2") (pinfunction "-_2") (pintype "passive"))
      (node (ref "Q18") (pin "3") (pinfunction "D_3") (pintype "passive"))
    )
    (net (code "159") (name "Net-(K19A-CA)") (class "Default")
      (node (ref "K19") (pin "3") (pinfunction "CA_3") (pintype "passive"))
      (node (ref "X3") (pin "19") (pinfunction "19_19") (pintype "passive"))
    )
    (net (code "160") (name "Net-(K19A-CB)") (class "Default")
      (node (ref "K19") (pin "4") (pinfunction "CB_4") (pintype "passive"))
      (node (ref "X2") (pin "19") (pinfunction "19_19") (pintype "passive"))
    )
    (net (code "161") (name "Net-(K19B--)") (class "Default")
      (node (ref "K19") (pin "2") (pinfunction "-_2") (pintype "passive"))
      (node (ref "Q19") (pin "3") (pinfunction "D_3") (pintype "passive"))
    )
    (net (code "162") (name "Net-(K20A-CA)") (class "Default")
      (node (ref "K20") (pin "3") (pinfunction "CA_3") (pintype "passive"))
      (node (ref "X3") (pin "20") (pinfunction "20_20") (pintype "passive"))
    )
    (net (code "163") (name "Net-(K20A-CB)") (class "Default")
      (node (ref "K20") (pin "4") (pinfunction "CB_4") (pintype "passive"))
      (node (ref "X2") (pin "20") (pinfunction "20_20") (pintype "passive"))
    )
    (net (code "164") (name "Net-(K20B--)") (class "Default")
      (node (ref "K20") (pin "2") (pinfunction "-_2") (pintype "passive"))
      (node (ref "Q20") (pin "3") (pinfunction "D_3") (pintype "passive"))
    )
    (net (code "165") (name "Net-(K21A-CA)") (class "Default")
      (node (ref "K21") (pin "3") (pinfunction "CA_3") (pintype "passive"))
      (node (ref "X3") (pin "21") (pinfunction "21_21") (pintype "passive"))
    )
    (net (code "166") (name "Net-(K21A-CB)") (class "Default")
      (node (ref "K21") (pin "4") (pinfunction "CB_4") (pintype "passive"))
      (node (ref "X2") (pin "21") (pinfunction "21_21") (pintype "passive"))
    )
    (net (code "167") (name "Net-(K21B--)") (class "Default")
      (node (ref "K21") (pin "2") (pinfunction "-_2") (pintype "passive"))
      (node (ref "Q21") (pin "3") (pinfunction "D_3") (pintype "passive"))
    )
    (net (code "168") (name "Net-(K22A-CA)") (class "Default")
      (node (ref "K22") (pin "3") (pinfunction "CA_3") (pintype "passive"))
      (node (ref "X3") (pin "22") (pinfunction "22_22") (pintype "passive"))
    )
    (net (code "169") (name "Net-(K22A-CB)") (class "Default")
      (node (ref "K22") (pin "4") (pinfunction "CB_4") (pintype "passive"))
      (node (ref "X2") (pin "22") (pinfunction "22_22") (pintype "passive"))
    )
    (net (code "170") (name "Net-(K22B--)") (class "Default")
      (node (ref "K22") (pin "2") (pinfunction "-_2") (pintype "passive"))
      (node (ref "Q22") (pin "3") (pinfunction "D_3") (pintype "passive"))
    )
    (net (code "171") (name "Net-(K23A-CA)") (class "Default")
      (node (ref "K23") (pin "3") (pinfunction "CA_3") (pintype "passive"))
      (node (ref "X3") (pin "23") (pinfunction "23_23") (pintype "passive"))
    )
    (net (code "172") (name "Net-(K23A-CB)") (class "Default")
      (node (ref "K23") (pin "4") (pinfunction "CB_4") (pintype "passive"))
      (node (ref "X2") (pin "23") (pinfunction "23_23") (pintype "passive"))
    )
    (net (code "173") (name "Net-(K23B--)") (class "Default")
      (node (ref "K23") (pin "2") (pinfunction "-_2") (pintype "passive"))
      (node (ref "Q23") (pin "3") (pinfunction "D_3") (pintype "passive"))
    )
    (net (code "174") (name "Net-(K24A-CA)") (class "Default")
      (node (ref "K24") (pin "3") (pinfunction "CA_3") (pintype "passive"))
      (node (ref "X3") (pin "24") (pinfunction "24_24") (pintype "passive"))
    )
    (net (code "175") (name "Net-(K24A-CB)") (class "Default")
      (node (ref "K24") (pin "4") (pinfunction "CB_4") (pintype "passive"))
      (node (ref "X2") (pin "24") (pinfunction "24_24") (pintype "passive"))
    )
    (net (code "176") (name "Net-(K24B--)") (class "Default")
      (node (ref "K24") (pin "2") (pinfunction "-_2") (pintype "passive"))
      (node (ref "Q24") (pin "3") (pinfunction "D_3") (pintype "passive"))
    )
    (net (code "177") (name "Net-(K25A-CA)") (class "Default")
      (node (ref "K25") (pin "3") (pinfunction "CA_3") (pintype "passive"))
      (node (ref "X3") (pin "25") (pinfunction "25_25") (pintype "passive"))
    )
    (net (code "178") (name "Net-(K25A-CB)") (class "Default")
      (node (ref "K25") (pin "4") (pinfunction "CB_4") (pintype "passive"))
      (node (ref "X2") (pin "25") (pinfunction "25_25") (pintype "passive"))
    )
    (net (code "179") (name "Net-(K25B--)") (class "Default")
      (node (ref "K25") (pin "2") (pinfunction "-_2") (pintype "passive"))
      (node (ref "Q25") (pin "3") (pinfunction "D_3") (pintype "passive"))
    )
    (net (code "180") (name "Net-(K26A-CA)") (class "Default")
      (node (ref "K26") (pin "3") (pinfunction "CA_3") (pintype "passive"))
      (node (ref "X3") (pin "26") (pinfunction "26_26") (pintype "passive"))
    )
    (net (code "181") (name "Net-(K26A-CB)") (class "Default")
      (node (ref "K26") (pin "4") (pinfunction "CB_4") (pintype "passive"))
      (node (ref "X2") (pin "26") (pinfunction "26_26") (pintype "passive"))
    )
    (net (code "182") (name "Net-(K26B--)") (class "Default")
      (node (ref "K26") (pin "2") (pinfunction "-_2") (pintype "passive"))
      (node (ref "Q26") (pin "3") (pinfunction "D_3") (pintype "passive"))
    )
    (net (code "183") (name "Net-(K27A-CA)") (class "Default")
      (node (ref "K27") (pin "3") (pinfunction "CA_3") (pintype "passive"))
      (node (ref "X3") (pin "27") (pinfunction "27_27") (pintype "passive"))
    )
    (net (code "184") (name "Net-(K27A-CB)") (class "Default")
      (node (ref "K27") (pin "4") (pinfunction "CB_4") (pintype "passive"))
      (node (ref "X2") (pin "27") (pinfunction "27_27") (pintype "passive"))
    )
    (net (code "185") (name "Net-(K27B--)") (class "Default")
      (node (ref "K27") (pin "2") (pinfunction "-_2") (pintype "passive"))
      (node (ref "Q27") (pin "3") (pinfunction "D_3") (pintype "passive"))
    )
    (net (code "186") (name "Net-(K28A-CA)") (class "Default")
      (node (ref "K28") (pin "3") (pinfunction "CA_3") (pintype "passive"))
      (node (ref "X3") (pin "28") (pinfunction "28_28") (pintype "passive"))
    )
    (net (code "187") (name "Net-(K28A-CB)") (class "Default")
      (node (ref "K28") (pin "4") (pinfunction "CB_4") (pintype "passive"))
      (node (ref "X2") (pin "28") (pinfunction "28_28") (pintype "passive"))
    )
    (net (code "188") (name "Net-(K28B--)") (class "Default")
      (node (ref "K28") (pin "2") (pinfunction "-_2") (pintype "passive"))
      (node (ref "Q28") (pin "3") (pinfunction "D_3") (pintype "passive"))
    )
    (net (code "189") (name "Net-(K29A-CA)") (class "Default")
      (node (ref "K29") (pin "3") (pinfunction "CA_3") (pintype "passive"))
      (node (ref "X3") (pin "29") (pinfunction "29_29") (pintype "passive"))
    )
    (net (code "190") (name "Net-(K29A-CB)") (class "Default")
      (node (ref "K29") (pin "4") (pinfunction "CB_4") (pintype "passive"))
      (node (ref "X2") (pin "29") (pinfunction "29_29") (pintype "passive"))
    )
    (net (code "191") (name "Net-(K29B--)") (class "Default")
      (node (ref "K29") (pin "2") (pinfunction "-_2") (pintype "passive"))
      (node (ref "Q29") (pin "3") (pinfunction "D_3") (pintype "passive"))
    )
    (net (code "192") (name "Net-(K30A-CA)") (class "Default")
      (node (ref "K30") (pin "3") (pinfunction "CA_3") (pintype "passive"))
      (node (ref "X3") (pin "30") (pinfunction "30_30") (pintype "passive"))
    )
    (net (code "193") (name "Net-(K30A-CB)") (class "Default")
      (node (ref "K30") (pin "4") (pinfunction "CB_4") (pintype "passive"))
      (node (ref "X2") (pin "30") (pinfunction "30_30") (pintype "passive"))
    )
    (net (code "194") (name "Net-(K30B--)") (class "Default")
      (node (ref "K30") (pin "2") (pinfunction "-_2") (pintype "passive"))
      (node (ref "Q30") (pin "3") (pinfunction "D_3") (pintype "passive"))
    )
    (net (code "195") (name "Net-(K31A-CA)") (class "Default")
      (node (ref "K31") (pin "3") (pinfunction "CA_3") (pintype "passive"))
      (node (ref "X3") (pin "31") (pinfunction "31_31") (pintype "passive"))
    )
    (net (code "196") (name "Net-(K31A-CB)") (class "Default")
      (node (ref "K31") (pin "4") (pinfunction "CB_4") (pintype "passive"))
      (node (ref "X2") (pin "31") (pinfunction "31_31") (pintype "passive"))
    )
    (net (code "197") (name "Net-(K31B--)") (class "Default")
      (node (ref "K31") (pin "2") (pinfunction "-_2") (pintype "passive"))
      (node (ref "Q31") (pin "3") (pinfunction "D_3") (pintype "passive"))
    )
    (net (code "198") (name "Net-(K32A-CA)") (class "Default")
      (node (ref "K32") (pin "3") (pinfunction "CA_3") (pintype "passive"))
      (node (ref "X3") (pin "32") (pinfunction "32_32") (pintype "passive"))
    )
    (net (code "199") (name "Net-(K32A-CB)") (class "Default")
      (node (ref "K32") (pin "4") (pinfunction "CB_4") (pintype "passive"))
      (node (ref "X2") (pin "32") (pinfunction "32_32") (pintype "passive"))
    )
    (net (code "200") (name "Net-(K32B--)") (class "Default")
      (node (ref "K32") (pin "2") (pinfunction "-_2") (pintype "passive"))
      (node (ref "Q32") (pin "3") (pinfunction "D_3") (pintype "passive"))
    )
    (net (code "201") (name "Net-(K33A-CA)") (class "Default")
      (node (ref "K33") (pin "3") (pinfunction "CA_3") (pintype "passive"))
      (node (ref "X3") (pin "33") (pinfunction "33_33") (pintype "passive"))
    )
    (net (code "202") (name "Net-(K33A-CB)") (class "Default")
      (node (ref "K33") (pin "4") (pinfunction "CB_4") (pintype "passive"))
      (node (ref "X2") (pin "33") (pinfunction "33_33") (pintype "passive"))
    )
    (net (code "203") (name "Net-(K33B--)") (class "Default")
      (node (ref "K33") (pin "2") (pinfunction "-_2") (pintype "passive"))
      (node (ref "Q33") (pin "3") (pinfunction "D_3") (pintype "passive"))
    )
    (net (code "204") (name "Net-(K34A-CA)") (class "Default")
      (node (ref "K34") (pin "3") (pinfunction "CA_3") (pintype "passive"))
      (node (ref "X3") (pin "34") (pinfunction "34_34") (pintype "passive"))
    )
    (net (code "205") (name "Net-(K34A-CB)") (class "Default")
      (node (ref "K34") (pin "4") (pinfunction "CB_4") (pintype "passive"))
      (node (ref "X2") (pin "34") (pinfunction "34_34") (pintype "passive"))
    )
    (net (code "206") (name "Net-(K34B--)") (class "Default")
      (node (ref "K34") (pin "2") (pinfunction "-_2") (pintype "passive"))
      (node (ref "Q34") (pin "3") (pinfunction "D_3") (pintype "passive"))
    )
    (net (code "207") (name "Net-(K35A-CA)") (class "Default")
      (node (ref "K35") (pin "3") (pinfunction "CA_3") (pintype "passive"))
      (node (ref "X3") (pin "35") (pinfunction "35_35") (pintype "passive"))
    )
    (net (code "208") (name "Net-(K35A-CB)") (class "Default")
      (node (ref "K35") (pin "4") (pinfunction "CB_4") (pintype "passive"))
      (node (ref "X2") (pin "35") (pinfunction "35_35") (pintype "passive"))
    )
    (net (code "209") (name "Net-(K35B--)") (class "Default")
      (node (ref "K35") (pin "2") (pinfunction "-_2") (pintype "passive"))
      (node (ref "Q35") (pin "3") (pinfunction "D_3") (pintype "passive"))
    )
    (net (code "210") (name "Net-(K36A-CA)") (class "Default")
      (node (ref "K36") (pin "3") (pinfunction "CA_3") (pintype "passive"))
      (node (ref "X3") (pin "36") (pinfunction "36_36") (pintype "passive"))
    )
    (net (code "211") (name "Net-(K36A-CB)") (class "Default")
      (node (ref "K36") (pin "4") (pinfunction "CB_4") (pintype "passive"))
      (node (ref "X2") (pin "36") (pinfunction "36_36") (pintype "passive"))
    )
    (net (code "212") (name "Net-(K36B--)") (class "Default")
      (node (ref "K36") (pin "2") (pinfunction "-_2") (pintype "passive"))
      (node (ref "Q36") (pin "3") (pinfunction "D_3") (pintype "passive"))
    )
    (net (code "213") (name "Net-(K37A-CA)") (class "Default")
      (node (ref "K37") (pin "3") (pinfunction "CA_3") (pintype "passive"))
      (node (ref "X3") (pin "37") (pinfunction "37_37") (pintype "passive"))
    )
    (net (code "214") (name "Net-(K37A-CB)") (class "Default")
      (node (ref "K37") (pin "4") (pinfunction "CB_4") (pintype "passive"))
      (node (ref "X2") (pin "37") (pinfunction "37_37") (pintype "passive"))
    )
    (net (code "215") (name "Net-(K37B--)") (class "Default")
      (node (ref "K37") (pin "2") (pinfunction "-_2") (pintype "passive"))
      (node (ref "Q37") (pin "3") (pinfunction "D_3") (pintype "passive"))
    )
    (net (code "216") (name "Net-(K38A-CA)") (class "Default")
      (node (ref "K38") (pin "3") (pinfunction "CA_3") (pintype "passive"))
      (node (ref "X3") (pin "38") (pinfunction "38_38") (pintype "passive"))
    )
    (net (code "217") (name "Net-(K38A-CB)") (class "Default")
      (node (ref "K38") (pin "4") (pinfunction "CB_4") (pintype "passive"))
      (node (ref "X2") (pin "38") (pinfunction "38_38") (pintype "passive"))
    )
    (net (code "218") (name "Net-(K38B--)") (class "Default")
      (node (ref "K38") (pin "2") (pinfunction "-_2") (pintype "passive"))
      (node (ref "Q38") (pin "3") (pinfunction "D_3") (pintype "passive"))
    )
    (net (code "219") (name "Net-(K39A-CA)") (class "Default")
      (node (ref "K39") (pin "3") (pinfunction "CA_3") (pintype "passive"))
      (node (ref "X3") (pin "39") (pinfunction "39_39") (pintype "passive"))
    )
    (net (code "220") (name "Net-(K39A-CB)") (class "Default")
      (node (ref "K39") (pin "4") (pinfunction "CB_4") (pintype "passive"))
      (node (ref "X2") (pin "39") (pinfunction "39_39") (pintype "passive"))
    )
    (net (code "221") (name "Net-(K39B--)") (class "Default")
      (node (ref "K39") (pin "2") (pinfunction "-_2") (pintype "passive"))
      (node (ref "Q39") (pin "3") (pinfunction "D_3") (pintype "passive"))
    )
    (net (code "222") (name "Net-(K40A-CA)") (class "Default")
      (node (ref "K40") (pin "3") (pinfunction "CA_3") (pintype "passive"))
      (node (ref "X3") (pin "40") (pinfunction "40_40") (pintype "passive"))
    )
    (net (code "223") (name "Net-(K40A-CB)") (class "Default")
      (node (ref "K40") (pin "4") (pinfunction "CB_4") (pintype "passive"))
      (node (ref "X2") (pin "40") (pinfunction "40_40") (pintype "passive"))
    )
    (net (code "224") (name "Net-(K40B--)") (class "Default")
      (node (ref "K40") (pin "2") (pinfunction "-_2") (pintype "passive"))
      (node (ref "Q40") (pin "3") (pinfunction "D_3") (pintype "passive"))
    )
    (net (code "225") (name "Net-(K41A-CA)") (class "Default")
      (node (ref "K41") (pin "3") (pinfunction "CA_3") (pintype "passive"))
      (node (ref "X3") (pin "41") (pinfunction "41_41") (pintype "passive"))
    )
    (net (code "226") (name "Net-(K41A-CB)") (class "Default")
      (node (ref "K41") (pin "4") (pinfunction "CB_4") (pintype "passive"))
      (node (ref "X2") (pin "41") (pinfunction "41_41") (pintype "passive"))
    )
    (net (code "227") (name "Net-(K41B--)") (class "Default")
      (node (ref "K41") (pin "2") (pinfunction "-_2") (pintype "passive"))
      (node (ref "Q41") (pin "3") (pinfunction "D_3") (pintype "passive"))
    )
    (net (code "228") (name "Net-(K42A-CA)") (class "Default")
      (node (ref "K42") (pin "3") (pinfunction "CA_3") (pintype "passive"))
      (node (ref "X3") (pin "42") (pinfunction "42_42") (pintype "passive"))
    )
    (net (code "229") (name "Net-(K42A-CB)") (class "Default")
      (node (ref "K42") (pin "4") (pinfunction "CB_4") (pintype "passive"))
      (node (ref "X2") (pin "42") (pinfunction "42_42") (pintype "passive"))
    )
    (net (code "230") (name "Net-(K42B--)") (class "Default")
      (node (ref "K42") (pin "2") (pinfunction "-_2") (pintype "passive"))
      (node (ref "Q42") (pin "3") (pinfunction "D_3") (pintype "passive"))
    )
    (net (code "231") (name "Net-(K43A-CA)") (class "Default")
      (node (ref "K43") (pin "3") (pinfunction "CA_3") (pintype "passive"))
      (node (ref "X3") (pin "43") (pinfunction "43_43") (pintype "passive"))
    )
    (net (code "232") (name "Net-(K43A-CB)") (class "Default")
      (node (ref "K43") (pin "4") (pinfunction "CB_4") (pintype "passive"))
      (node (ref "X2") (pin "43") (pinfunction "43_43") (pintype "passive"))
    )
    (net (code "233") (name "Net-(K43B--)") (class "Default")
      (node (ref "K43") (pin "2") (pinfunction "-_2") (pintype "passive"))
      (node (ref "Q43") (pin "3") (pinfunction "D_3") (pintype "passive"))
    )
    (net (code "234") (name "Net-(K44A-CA)") (class "Default")
      (node (ref "K44") (pin "3") (pinfunction "CA_3") (pintype "passive"))
      (node (ref "X3") (pin "44") (pinfunction "44_44") (pintype "passive"))
    )
    (net (code "235") (name "Net-(K44A-CB)") (class "Default")
      (node (ref "K44") (pin "4") (pinfunction "CB_4") (pintype "passive"))
      (node (ref "X2") (pin "44") (pinfunction "44_44") (pintype "passive"))
    )
    (net (code "236") (name "Net-(K44B--)") (class "Default")
      (node (ref "K44") (pin "2") (pinfunction "-_2") (pintype "passive"))
      (node (ref "Q44") (pin "3") (pinfunction "D_3") (pintype "passive"))
    )
    (net (code "237") (name "Net-(K45A-CA)") (class "Default")
      (node (ref "K45") (pin "3") (pinfunction "CA_3") (pintype "passive"))
      (node (ref "X3") (pin "45") (pinfunction "45_45") (pintype "passive"))
    )
    (net (code "238") (name "Net-(K45A-CB)") (class "Default")
      (node (ref "K45") (pin "4") (pinfunction "CB_4") (pintype "passive"))
      (node (ref "X2") (pin "45") (pinfunction "45_45") (pintype "passive"))
    )
    (net (code "239") (name "Net-(K45B--)") (class "Default")
      (node (ref "K45") (pin "2") (pinfunction "-_2") (pintype "passive"))
      (node (ref "Q45") (pin "3") (pinfunction "D_3") (pintype "passive"))
    )
    (net (code "240") (name "Net-(K46A-CA)") (class "Default")
      (node (ref "K46") (pin "3") (pinfunction "CA_3") (pintype "passive"))
      (node (ref "X3") (pin "46") (pinfunction "46_46") (pintype "passive"))
    )
    (net (code "241") (name "Net-(K46A-CB)") (class "Default")
      (node (ref "K46") (pin "4") (pinfunction "CB_4") (pintype "passive"))
      (node (ref "X2") (pin "46") (pinfunction "46_46") (pintype "passive"))
    )
    (net (code "242") (name "Net-(K46B--)") (class "Default")
      (node (ref "K46") (pin "2") (pinfunction "-_2") (pintype "passive"))
      (node (ref "Q46") (pin "3") (pinfunction "D_3") (pintype "passive"))
    )
    (net (code "243") (name "Net-(K47A-CA)") (class "Default")
      (node (ref "K47") (pin "3") (pinfunction "CA_3") (pintype "passive"))
      (node (ref "X3") (pin "47") (pinfunction "47_47") (pintype "passive"))
    )
    (net (code "244") (name "Net-(K47A-CB)") (class "Default")
      (node (ref "K47") (pin "4") (pinfunction "CB_4") (pintype "passive"))
      (node (ref "X2") (pin "47") (pinfunction "47_47") (pintype "passive"))
    )
    (net (code "245") (name "Net-(K47B--)") (class "Default")
      (node (ref "K47") (pin "2") (pinfunction "-_2") (pintype "passive"))
      (node (ref "Q47") (pin "3") (pinfunction "D_3") (pintype "passive"))
    )
    (net (code "246") (name "Net-(K48A-CA)") (class "Default")
      (node (ref "K48") (pin "3") (pinfunction "CA_3") (pintype "passive"))
      (node (ref "X3") (pin "48") (pinfunction "48_48") (pintype "passive"))
    )
    (net (code "247") (name "Net-(K48A-CB)") (class "Default")
      (node (ref "K48") (pin "4") (pinfunction "CB_4") (pintype "passive"))
      (node (ref "X2") (pin "48") (pinfunction "48_48") (pintype "passive"))
    )
    (net (code "248") (name "Net-(K48B--)") (class "Default")
      (node (ref "K48") (pin "2") (pinfunction "-_2") (pintype "passive"))
      (node (ref "Q48") (pin "3") (pinfunction "D_3") (pintype "passive"))
    )
    (net (code "249") (name "Net-(K49A-CA)") (class "Default")
      (node (ref "K49") (pin "3") (pinfunction "CA_3") (pintype "passive"))
      (node (ref "X3") (pin "49") (pinfunction "49_49") (pintype "passive"))
    )
    (net (code "250") (name "Net-(K49A-CB)") (class "Default")
      (node (ref "K49") (pin "4") (pinfunction "CB_4") (pintype "passive"))
      (node (ref "X2") (pin "49") (pinfunction "49_49") (pintype "passive"))
    )
    (net (code "251") (name "Net-(K49B--)") (class "Default")
      (node (ref "K49") (pin "2") (pinfunction "-_2") (pintype "passive"))
      (node (ref "Q49") (pin "3") (pinfunction "D_3") (pintype "passive"))
    )
    (net (code "252") (name "Net-(K50A-CA)") (class "Default")
      (node (ref "K50") (pin "3") (pinfunction "CA_3") (pintype "passive"))
      (node (ref "X3") (pin "50") (pinfunction "50_50") (pintype "passive"))
    )
    (net (code "253") (name "Net-(K50A-CB)") (class "Default")
      (node (ref "K50") (pin "4") (pinfunction "CB_4") (pintype "passive"))
      (node (ref "X2") (pin "50") (pinfunction "50_50") (pintype "passive"))
    )
    (net (code "254") (name "Net-(K50B--)") (class "Default")
      (node (ref "K50") (pin "2") (pinfunction "-_2") (pintype "passive"))
      (node (ref "Q50") (pin "3") (pinfunction "D_3") (pintype "passive"))
    )
    (net (code "255") (name "Net-(K51A-CA)") (class "Default")
      (node (ref "K51") (pin "3") (pinfunction "CA_3") (pintype "passive"))
      (node (ref "X3") (pin "51") (pinfunction "51_51") (pintype "passive"))
    )
    (net (code "256") (name "Net-(K51A-CB)") (class "Default")
      (node (ref "K51") (pin "4") (pinfunction "CB_4") (pintype "passive"))
      (node (ref "X2") (pin "51") (pinfunction "51_51") (pintype "passive"))
    )
    (net (code "257") (name "Net-(K51B--)") (class "Default")
      (node (ref "K51") (pin "2") (pinfunction "-_2") (pintype "passive"))
      (node (ref "Q51") (pin "3") (pinfunction "D_3") (pintype "passive"))
    )
    (net (code "258") (name "Net-(K52A-CA)") (class "Default")
      (node (ref "K52") (pin "3") (pinfunction "CA_3") (pintype "passive"))
      (node (ref "X3") (pin "52") (pinfunction "52_52") (pintype "passive"))
    )
    (net (code "259") (name "Net-(K52A-CB)") (class "Default")
      (node (ref "K52") (pin "4") (pinfunction "CB_4") (pintype "passive"))
      (node (ref "X2") (pin "52") (pinfunction "52_52") (pintype "passive"))
    )
    (net (code "260") (name "Net-(K52B--)") (class "Default")
      (node (ref "K52") (pin "2") (pinfunction "-_2") (pintype "passive"))
      (node (ref "Q52") (pin "3") (pinfunction "D_3") (pintype "passive"))
    )
    (net (code "261") (name "Net-(K53A-CA)") (class "Default")
      (node (ref "K53") (pin "3") (pinfunction "CA_3") (pintype "passive"))
      (node (ref "X3") (pin "53") (pinfunction "53_53") (pintype "passive"))
    )
    (net (code "262") (name "Net-(K53A-CB)") (class "Default")
      (node (ref "K53") (pin "4") (pinfunction "CB_4") (pintype "passive"))
      (node (ref "X2") (pin "53") (pinfunction "53_53") (pintype "passive"))
    )
    (net (code "263") (name "Net-(K53B--)") (class "Default")
      (node (ref "K53") (pin "2") (pinfunction "-_2") (pintype "passive"))
      (node (ref "Q53") (pin "3") (pinfunction "D_3") (pintype "passive"))
    )
    (net (code "264") (name "Net-(K54A-CA)") (class "Default")
      (node (ref "K54") (pin "3") (pinfunction "CA_3") (pintype "passive"))
      (node (ref "X3") (pin "54") (pinfunction "54_54") (pintype "passive"))
    )
    (net (code "265") (name "Net-(K54A-CB)") (class "Default")
      (node (ref "K54") (pin "4") (pinfunction "CB_4") (pintype "passive"))
      (node (ref "X2") (pin "54") (pinfunction "54_54") (pintype "passive"))
    )
    (net (code "266") (name "Net-(K54B--)") (class "Default")
      (node (ref "K54") (pin "2") (pinfunction "-_2") (pintype "passive"))
      (node (ref "Q54") (pin "3") (pinfunction "D_3") (pintype "passive"))
    )
    (net (code "267") (name "Net-(K55A-CA)") (class "Default")
      (node (ref "K55") (pin "3") (pinfunction "CA_3") (pintype "passive"))
      (node (ref "X3") (pin "55") (pinfunction "55_55") (pintype "passive"))
    )
    (net (code "268") (name "Net-(K55A-CB)") (class "Default")
      (node (ref "K55") (pin "4") (pinfunction "CB_4") (pintype "passive"))
      (node (ref "X2") (pin "55") (pinfunction "55_55") (pintype "passive"))
    )
    (net (code "269") (name "Net-(K55B--)") (class "Default")
      (node (ref "K55") (pin "2") (pinfunction "-_2") (pintype "passive"))
      (node (ref "Q55") (pin "3") (pinfunction "D_3") (pintype "passive"))
    )
    (net (code "270") (name "Net-(K56A-CA)") (class "Default")
      (node (ref "K56") (pin "3") (pinfunction "CA_3") (pintype "passive"))
      (node (ref "X3") (pin "56") (pinfunction "56_56") (pintype "passive"))
    )
    (net (code "271") (name "Net-(K56A-CB)") (class "Default")
      (node (ref "K56") (pin "4") (pinfunction "CB_4") (pintype "passive"))
      (node (ref "X2") (pin "56") (pinfunction "56_56") (pintype "passive"))
    )
    (net (code "272") (name "Net-(K56B--)") (class "Default")
      (node (ref "K56") (pin "2") (pinfunction "-_2") (pintype "passive"))
      (node (ref "Q56") (pin "3") (pinfunction "D_3") (pintype "passive"))
    )
    (net (code "273") (name "Net-(K57A-CA)") (class "Default")
      (node (ref "K57") (pin "3") (pinfunction "CA_3") (pintype "passive"))
      (node (ref "X3") (pin "57") (pinfunction "57_57") (pintype "passive"))
    )
    (net (code "274") (name "Net-(K57A-CB)") (class "Default")
      (node (ref "K57") (pin "4") (pinfunction "CB_4") (pintype "passive"))
      (node (ref "X2") (pin "57") (pinfunction "57_57") (pintype "passive"))
    )
    (net (code "275") (name "Net-(K57B--)") (class "Default")
      (node (ref "K57") (pin "2") (pinfunction "-_2") (pintype "passive"))
      (node (ref "Q57") (pin "3") (pinfunction "D_3") (pintype "passive"))
    )
    (net (code "276") (name "Net-(K58A-CA)") (class "Default")
      (node (ref "K58") (pin "3") (pinfunction "CA_3") (pintype "passive"))
      (node (ref "X3") (pin "58") (pinfunction "58_58") (pintype "passive"))
    )
    (net (code "277") (name "Net-(K58A-CB)") (class "Default")
      (node (ref "K58") (pin "4") (pinfunction "CB_4") (pintype "passive"))
      (node (ref "X2") (pin "58") (pinfunction "58_58") (pintype "passive"))
    )
    (net (code "278") (name "Net-(K58B--)") (class "Default")
      (node (ref "K58") (pin "2") (pinfunction "-_2") (pintype "passive"))
      (node (ref "Q58") (pin "3") (pinfunction "D_3") (pintype "passive"))
    )
    (net (code "279") (name "Net-(K59A-CA)") (class "Default")
      (node (ref "K59") (pin "3") (pinfunction "CA_3") (pintype "passive"))
      (node (ref "X3") (pin "59") (pinfunction "59_59") (pintype "passive"))
    )
    (net (code "280") (name "Net-(K59A-CB)") (class "Default")
      (node (ref "K59") (pin "4") (pinfunction "CB_4") (pintype "passive"))
      (node (ref "X2") (pin "59") (pinfunction "59_59") (pintype "passive"))
    )
    (net (code "281") (name "Net-(K59B--)") (class "Default")
      (node (ref "K59") (pin "2") (pinfunction "-_2") (pintype "passive"))
      (node (ref "Q59") (pin "3") (pinfunction "D_3") (pintype "passive"))
    )
    (net (code "282") (name "Net-(K60A-CA)") (class "Default")
      (node (ref "K60") (pin "3") (pinfunction "CA_3") (pintype "passive"))
      (node (ref "X3") (pin "60") (pinfunction "60_60") (pintype "passive"))
    )
    (net (code "283") (name "Net-(K60A-CB)") (class "Default")
      (node (ref "K60") (pin "4") (pinfunction "CB_4") (pintype "passive"))
      (node (ref "X2") (pin "60") (pinfunction "60_60") (pintype "passive"))
    )
    (net (code "284") (name "Net-(K60B--)") (class "Default")
      (node (ref "K60") (pin "2") (pinfunction "-_2") (pintype "passive"))
      (node (ref "Q60") (pin "3") (pinfunction "D_3") (pintype "passive"))
    )
    (net (code "285") (name "Net-(K61A-CA)") (class "Default")
      (node (ref "K61") (pin "3") (pinfunction "CA_3") (pintype "passive"))
      (node (ref "X3") (pin "61") (pinfunction "61_61") (pintype "passive"))
    )
    (net (code "286") (name "Net-(K61A-CB)") (class "Default")
      (node (ref "K61") (pin "4") (pinfunction "CB_4") (pintype "passive"))
      (node (ref "X2") (pin "61") (pinfunction "61_61") (pintype "passive"))
    )
    (net (code "287") (name "Net-(K61B--)") (class "Default")
      (node (ref "K61") (pin "2") (pinfunction "-_2") (pintype "passive"))
      (node (ref "Q61") (pin "3") (pinfunction "D_3") (pintype "passive"))
    )
    (net (code "288") (name "Net-(K62A-CA)") (class "Default")
      (node (ref "K62") (pin "3") (pinfunction "CA_3") (pintype "passive"))
      (node (ref "X3") (pin "62") (pinfunction "62_62") (pintype "passive"))
    )
    (net (code "289") (name "Net-(K62A-CB)") (class "Default")
      (node (ref "K62") (pin "4") (pinfunction "CB_4") (pintype "passive"))
      (node (ref "X2") (pin "62") (pinfunction "62_62") (pintype "passive"))
    )
    (net (code "290") (name "Net-(K62B--)") (class "Default")
      (node (ref "K62") (pin "2") (pinfunction "-_2") (pintype "passive"))
      (node (ref "Q62") (pin "3") (pinfunction "D_3") (pintype "passive"))
    )
    (net (code "291") (name "Net-(K63A-CA)") (class "Default")
      (node (ref "K63") (pin "3") (pinfunction "CA_3") (pintype "passive"))
      (node (ref "X3") (pin "63") (pinfunction "63_63") (pintype "passive"))
    )
    (net (code "292") (name "Net-(K63A-CB)") (class "Default")
      (node (ref "K63") (pin "4") (pinfunction "CB_4") (pintype "passive"))
      (node (ref "X2") (pin "63") (pinfunction "63_63") (pintype "passive"))
    )
    (net (code "293") (name "Net-(K63B--)") (class "Default")
      (node (ref "K63") (pin "2") (pinfunction "-_2") (pintype "passive"))
      (node (ref "Q63") (pin "3") (pinfunction "D_3") (pintype "passive"))
    )
    (net (code "294") (name "Net-(K64A-CA)") (class "Default")
      (node (ref "K64") (pin "3") (pinfunction "CA_3") (pintype "passive"))
      (node (ref "X3") (pin "64") (pinfunction "64_64") (pintype "passive"))
    )
    (net (code "295") (name "Net-(K64A-CB)") (class "Default")
      (node (ref "K64") (pin "4") (pinfunction "CB_4") (pintype "passive"))
      (node (ref "X2") (pin "64") (pinfunction "64_64") (pintype "passive"))
    )
    (net (code "296") (name "Net-(K64B--)") (class "Default")
      (node (ref "K64") (pin "2") (pinfunction "-_2") (pintype "passive"))
      (node (ref "Q64") (pin "3") (pinfunction "D_3") (pintype "passive"))
    )
  )
)
